# MC-10_Schematics.net
KiCad netlist of a schematic drawn in EAGLE
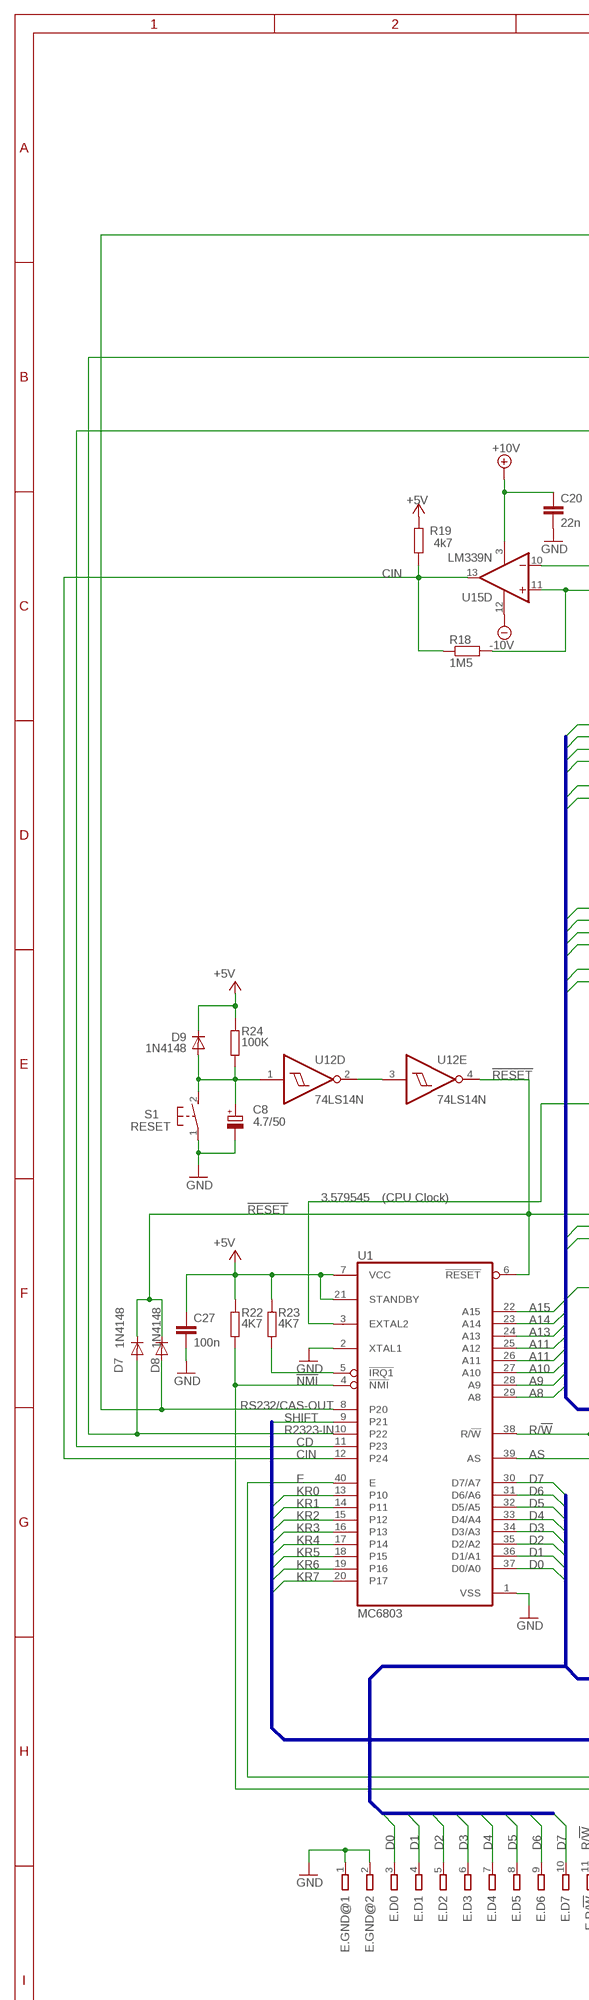
[diagram p0: schematic, sheet 1, part 1 of 2]
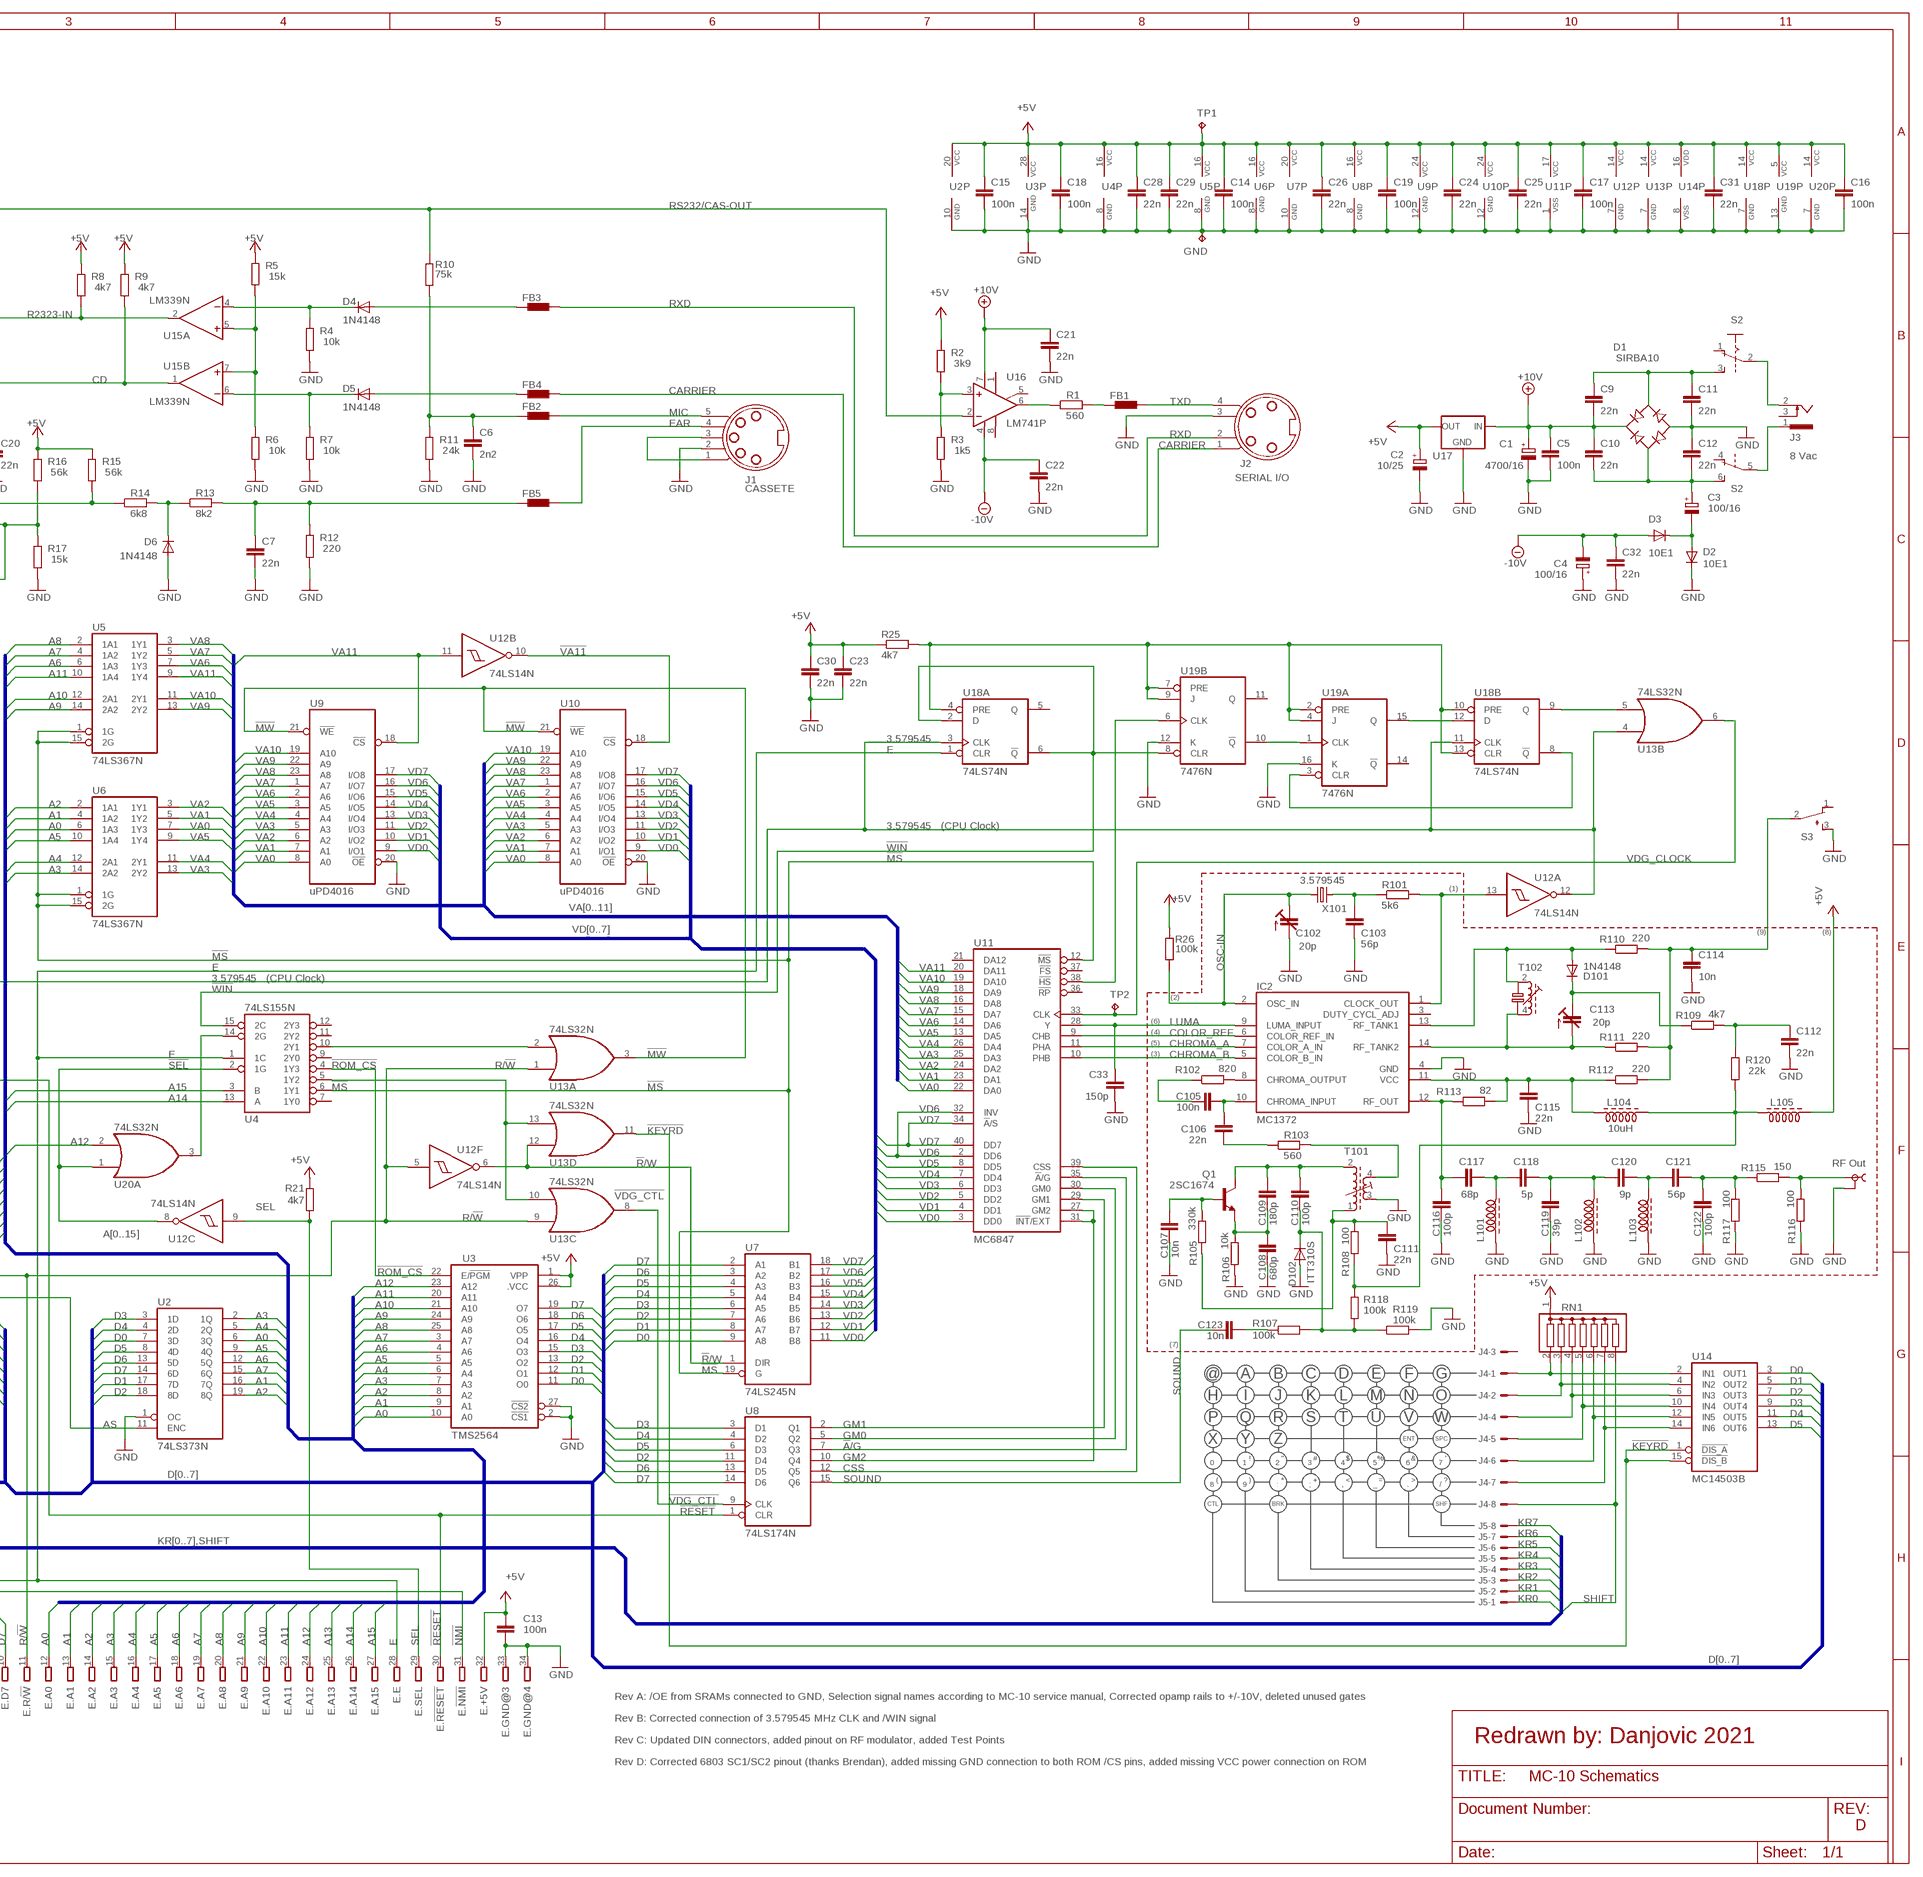
[diagram p1: schematic, sheet 1, part 2 of 2]

(export (version "E")
  (design (tool "Eeschema 10.0.6"))
  (components
    (comp (ref "C1")
      (value "4700/16")
      (footprint "eagle-import:E7,5-18")
      (libsource (lib "eagle-import") (part "CPOL-EUE7.5-18"))
    )
    (comp (ref "C2")
      (value "10/25")
      (footprint "eagle-import:E1,8-4")
      (libsource (lib "eagle-import") (part "CPOL-EUE1.8-4"))
    )
    (comp (ref "C3")
      (value "100/16")
      (footprint "eagle-import:E15-5")
      (libsource (lib "eagle-import") (part "CPOL-EUE15-5AXIAL"))
    )
    (comp (ref "C4")
      (value "100/16")
      (footprint "eagle-import:E15-5")
      (libsource (lib "eagle-import") (part "CPOL-EUE15-5AXIAL"))
    )
    (comp (ref "C5")
      (value "100n")
      (footprint "eagle-import:C050-024X044")
      (libsource (lib "eagle-import") (part "C-EU050-024X044"))
    )
    (comp (ref "C6")
      (value "2n2")
      (footprint "eagle-import:C050-024X044")
      (libsource (lib "eagle-import") (part "C-EU050-024X044"))
    )
    (comp (ref "C7")
      (value "22n")
      (footprint "eagle-import:C050-024X044")
      (libsource (lib "eagle-import") (part "C-EU050-024X044"))
    )
    (comp (ref "C8")
      (value "4.7/50")
      (footprint "eagle-import:E1,8-4")
      (libsource (lib "eagle-import") (part "CPOL-EUE1.8-4"))
    )
    (comp (ref "C9")
      (value "22n")
      (footprint "eagle-import:C050-024X044")
      (libsource (lib "eagle-import") (part "C-EU050-024X044"))
    )
    (comp (ref "C10")
      (value "22n")
      (footprint "eagle-import:C050-024X044")
      (libsource (lib "eagle-import") (part "C-EU050-024X044"))
    )
    (comp (ref "C11")
      (value "22n")
      (footprint "eagle-import:C050-024X044")
      (libsource (lib "eagle-import") (part "C-EU050-024X044"))
    )
    (comp (ref "C12")
      (value "22n")
      (footprint "eagle-import:C050-024X044")
      (libsource (lib "eagle-import") (part "C-EU050-024X044"))
    )
    (comp (ref "C13")
      (value "100n")
      (footprint "eagle-import:C050-024X044")
      (libsource (lib "eagle-import") (part "C-EU050-024X044"))
    )
    (comp (ref "C14")
      (value "100n")
      (footprint "eagle-import:C050-024X044")
      (libsource (lib "eagle-import") (part "C-EU050-024X044"))
    )
    (comp (ref "C15")
      (value "100n")
      (footprint "eagle-import:C050-024X044")
      (libsource (lib "eagle-import") (part "C-EU050-024X044"))
    )
    (comp (ref "C16")
      (value "100n")
      (footprint "eagle-import:C050-024X044")
      (libsource (lib "eagle-import") (part "C-EU050-024X044"))
    )
    (comp (ref "C17")
      (value "100n")
      (footprint "eagle-import:C050-024X044")
      (libsource (lib "eagle-import") (part "C-EU050-024X044"))
    )
    (comp (ref "C18")
      (value "100n")
      (footprint "eagle-import:C050-024X044")
      (libsource (lib "eagle-import") (part "C-EU050-024X044"))
    )
    (comp (ref "C19")
      (value "100n")
      (footprint "eagle-import:C050-024X044")
      (libsource (lib "eagle-import") (part "C-EU050-024X044"))
    )
    (comp (ref "C20")
      (value "22n")
      (footprint "eagle-import:C050-024X044")
      (libsource (lib "eagle-import") (part "C-EU050-024X044"))
    )
    (comp (ref "C21")
      (value "22n")
      (footprint "eagle-import:C050-024X044")
      (libsource (lib "eagle-import") (part "C-EU050-024X044"))
    )
    (comp (ref "C22")
      (value "22n")
      (footprint "eagle-import:C050-024X044")
      (libsource (lib "eagle-import") (part "C-EU050-024X044"))
    )
    (comp (ref "C23")
      (value "22n")
      (footprint "eagle-import:C050-024X044")
      (libsource (lib "eagle-import") (part "C-EU050-024X044"))
    )
    (comp (ref "C24")
      (value "22n")
      (footprint "eagle-import:C050-024X044")
      (libsource (lib "eagle-import") (part "C-EU050-024X044"))
    )
    (comp (ref "C25")
      (value "22n")
      (footprint "eagle-import:C050-024X044")
      (libsource (lib "eagle-import") (part "C-EU050-024X044"))
    )
    (comp (ref "C26")
      (value "22n")
      (footprint "eagle-import:C050-024X044")
      (libsource (lib "eagle-import") (part "C-EU050-024X044"))
    )
    (comp (ref "C27")
      (value "100n")
      (footprint "eagle-import:C050-024X044")
      (libsource (lib "eagle-import") (part "C-EU050-024X044"))
    )
    (comp (ref "C28")
      (value "22n")
      (footprint "eagle-import:C050-024X044")
      (libsource (lib "eagle-import") (part "C-EU050-024X044"))
    )
    (comp (ref "C29")
      (value "22n")
      (footprint "eagle-import:C050-024X044")
      (libsource (lib "eagle-import") (part "C-EU050-024X044"))
    )
    (comp (ref "C30")
      (value "22n")
      (footprint "eagle-import:C050-024X044")
      (libsource (lib "eagle-import") (part "C-EU050-024X044"))
    )
    (comp (ref "C31")
      (value "22n")
      (footprint "eagle-import:C050-024X044")
      (libsource (lib "eagle-import") (part "C-EU050-024X044"))
    )
    (comp (ref "C32")
      (value "22n")
      (footprint "eagle-import:C050-024X044")
      (libsource (lib "eagle-import") (part "C-EU050-024X044"))
    )
    (comp (ref "C33")
      (value "150p")
      (footprint "eagle-import:C025-024X044")
      (libsource (lib "eagle-import") (part "C-EU025-024X044"))
    )
    (comp (ref "C102")
      (value "20p")
      (footprint "eagle-import:3008")
      (libsource (lib "eagle-import") (part "C-TRIMM3008"))
    )
    (comp (ref "C103")
      (value "56p")
      (footprint "eagle-import:C025-024X044")
      (libsource (lib "eagle-import") (part "C-EU025-024X044"))
    )
    (comp (ref "C105")
      (value "100n")
      (footprint "eagle-import:C050-024X044")
      (libsource (lib "eagle-import") (part "C-EU050-024X044"))
    )
    (comp (ref "C106")
      (value "22n")
      (footprint "eagle-import:C050-024X044")
      (libsource (lib "eagle-import") (part "C-EU050-024X044"))
    )
    (comp (ref "C107")
      (value "10n")
      (footprint "eagle-import:C025-024X044")
      (libsource (lib "eagle-import") (part "C-EU025-024X044"))
    )
    (comp (ref "C108")
      (value "680p")
      (footprint "eagle-import:C025-024X044")
      (libsource (lib "eagle-import") (part "C-EU025-024X044"))
    )
    (comp (ref "C109")
      (value "180p")
      (footprint "eagle-import:C025-024X044")
      (libsource (lib "eagle-import") (part "C-EU025-024X044"))
    )
    (comp (ref "C110")
      (value "100p")
      (footprint "eagle-import:C025-024X044")
      (libsource (lib "eagle-import") (part "C-EU025-024X044"))
    )
    (comp (ref "C111")
      (value "22n")
      (footprint "eagle-import:C025-024X044")
      (libsource (lib "eagle-import") (part "C-EU025-024X044"))
    )
    (comp (ref "C112")
      (value "22n")
      (footprint "eagle-import:C025-024X044")
      (libsource (lib "eagle-import") (part "C-EU025-024X044"))
    )
    (comp (ref "C113")
      (value "20p")
      (footprint "eagle-import:3008")
      (libsource (lib "eagle-import") (part "C-TRIMM3008"))
    )
    (comp (ref "C114")
      (value "10n")
      (footprint "eagle-import:C025-024X044")
      (libsource (lib "eagle-import") (part "C-EU025-024X044"))
    )
    (comp (ref "C115")
      (value "22n")
      (footprint "eagle-import:C025-024X044")
      (libsource (lib "eagle-import") (part "C-EU025-024X044"))
    )
    (comp (ref "C116")
      (value "100p")
      (footprint "eagle-import:C025-024X044")
      (libsource (lib "eagle-import") (part "C-EU025-024X044"))
    )
    (comp (ref "C117")
      (value "68p")
      (footprint "eagle-import:C025-024X044")
      (libsource (lib "eagle-import") (part "C-EU025-024X044"))
    )
    (comp (ref "C118")
      (value "5p")
      (footprint "eagle-import:C025-024X044")
      (libsource (lib "eagle-import") (part "C-EU025-024X044"))
    )
    (comp (ref "C119")
      (value "39p")
      (footprint "eagle-import:C025-024X044")
      (libsource (lib "eagle-import") (part "C-EU025-024X044"))
    )
    (comp (ref "C120")
      (value "9p")
      (footprint "eagle-import:C025-024X044")
      (libsource (lib "eagle-import") (part "C-EU025-024X044"))
    )
    (comp (ref "C121")
      (value "56p")
      (footprint "eagle-import:C025-024X044")
      (libsource (lib "eagle-import") (part "C-EU025-024X044"))
    )
    (comp (ref "C122")
      (value "100p")
      (footprint "eagle-import:C025-024X044")
      (libsource (lib "eagle-import") (part "C-EU025-024X044"))
    )
    (comp (ref "C123")
      (value "10n")
      (footprint "eagle-import:C025-024X044")
      (libsource (lib "eagle-import") (part "C-EU025-024X044"))
    )
    (comp (ref "D1")
      (value "SIRBA10")
      (footprint "eagle-import:SKBB")
      (libsource (lib "eagle-import") (part "RECTIFIER-SKBB"))
    )
    (comp (ref "D2")
      (value "10E1")
      (footprint "eagle-import:D-7.5")
      (libsource (lib "eagle-import") (part "DIODE-D-7.5"))
    )
    (comp (ref "D3")
      (value "10E1")
      (footprint "eagle-import:D-7.5")
      (libsource (lib "eagle-import") (part "DIODE-D-7.5"))
    )
    (comp (ref "D4")
      (value "1N4148")
      (footprint "eagle-import:DO35-7")
      (libsource (lib "eagle-import") (part "1N4148DO35-7"))
    )
    (comp (ref "D5")
      (value "1N4148")
      (footprint "eagle-import:DO35-7")
      (libsource (lib "eagle-import") (part "1N4148DO35-7"))
    )
    (comp (ref "D6")
      (value "1N4148")
      (footprint "eagle-import:DO35-7")
      (libsource (lib "eagle-import") (part "1N4148DO35-7"))
    )
    (comp (ref "D7")
      (value "1N4148")
      (footprint "eagle-import:DO35-7")
      (libsource (lib "eagle-import") (part "1N4148DO35-7"))
    )
    (comp (ref "D8")
      (value "1N4148")
      (footprint "eagle-import:DO35-7")
      (libsource (lib "eagle-import") (part "1N4148DO35-7"))
    )
    (comp (ref "D9")
      (value "1N4148")
      (footprint "eagle-import:DO35-7")
      (libsource (lib "eagle-import") (part "1N4148DO35-7"))
    )
    (comp (ref "D101")
      (value "1N4148")
      (footprint "eagle-import:DO35-7")
      (libsource (lib "eagle-import") (part "1N4148DO35-7"))
    )
    (comp (ref "D102")
      (value "ITT310S")
      (footprint "eagle-import:DO35-7")
      (libsource (lib "eagle-import") (part "1N4148DO35-7"))
    )
    (comp (ref "E.")
      (value "EXPANSION")
      (footprint "eagle-import:EXPANSION_PORT")
      (libsource (lib "eagle-import") (part "EXPANSION"))
    )
    (comp (ref "FB1")
      (value "BL01RN1A")
      (footprint "eagle-import:BL01RN1A")
      (libsource (lib "eagle-import") (part "BL01RN1A"))
    )
    (comp (ref "FB2")
      (value "BL01RN1A")
      (footprint "eagle-import:BL01RN1A")
      (libsource (lib "eagle-import") (part "BL01RN1A"))
    )
    (comp (ref "FB3")
      (value "BL01RN1A")
      (footprint "eagle-import:BL01RN1A")
      (libsource (lib "eagle-import") (part "BL01RN1A"))
    )
    (comp (ref "FB4")
      (value "BL01RN1A")
      (footprint "eagle-import:BL01RN1A")
      (libsource (lib "eagle-import") (part "BL01RN1A"))
    )
    (comp (ref "FB5")
      (value "BL01RN1A")
      (footprint "eagle-import:BL01RN1A")
      (libsource (lib "eagle-import") (part "BL01RN1A"))
    )
    (comp (ref "GND")
      (value "TPPAD1-13")
      (footprint "eagle-import:P1-13")
      (libsource (lib "eagle-import") (part "TPPAD1-13"))
    )
    (comp (ref "IC2")
      (value "MC1372")
      (footprint "eagle-import:DIL14")
      (libsource (lib "eagle-import") (part "MC1372"))
    )
    (comp (ref "J1")
      (value "DS-4-05")
      (footprint "eagle-import:MC-10_DIN05S")
      (libsource (lib "eagle-import") (part "DS-4-05"))
    )
    (comp (ref "J2")
      (value "DS-4-04")
      (footprint "eagle-import:MC-10_DIN04S")
      (libsource (lib "eagle-import") (part "DS-4-04"))
    )
    (comp (ref "J3")
      (value "733980-62")
      (footprint "eagle-import:733980-62")
      (libsource (lib "eagle-import") (part "73398?0-62"))
    )
    (comp (ref "J4")
      (value "22-27-2081-08")
      (footprint "eagle-import:6410-08")
      (libsource (lib "eagle-import") (part "22-?-0827-2081"))
    )
    (comp (ref "J5")
      (value "22-27-2081-08")
      (footprint "eagle-import:6410-08")
      (libsource (lib "eagle-import") (part "22-?-0827-2081"))
    )
    (comp (ref "L101")
      (value "Z15/05CCW")
      (footprint "eagle-import:Z15_05")
      (libsource (lib "eagle-import") (part "Z?CCW15/05"))
    )
    (comp (ref "L102")
      (value "Z15/05CCW")
      (footprint "eagle-import:Z15_05")
      (libsource (lib "eagle-import") (part "Z?CCW15/05"))
    )
    (comp (ref "L103")
      (value "Z15/05CCW")
      (footprint "eagle-import:Z15_05")
      (libsource (lib "eagle-import") (part "Z?CCW15/05"))
    )
    (comp (ref "L104")
      (value "10uH")
      (footprint "eagle-import:Z15_05")
      (libsource (lib "eagle-import") (part "Z?CCW15/05"))
    )
    (comp (ref "L105")
      (value "10uH")
      (footprint "eagle-import:Z15_05")
      (libsource (lib "eagle-import") (part "Z?CCW15/05"))
    )
    (comp (ref "Q1")
      (value "2SC1674")
      (footprint "eagle-import:TO92-CEB")
      (libsource (lib "eagle-import") (part "-NPN-TO92-CEBBF494"))
    )
    (comp (ref "R1")
      (value "560")
      (footprint "eagle-import:0204_7")
      (libsource (lib "eagle-import") (part "R-EU_0204/7"))
    )
    (comp (ref "R2")
      (value "3k9")
      (footprint "eagle-import:0204_7")
      (libsource (lib "eagle-import") (part "R-EU_0204/7"))
    )
    (comp (ref "R3")
      (value "1k5")
      (footprint "eagle-import:0204_7")
      (libsource (lib "eagle-import") (part "R-EU_0204/7"))
    )
    (comp (ref "R4")
      (value "10k")
      (footprint "eagle-import:0204_7")
      (libsource (lib "eagle-import") (part "R-EU_0204/7"))
    )
    (comp (ref "R5")
      (value "15k")
      (footprint "eagle-import:0204_7")
      (libsource (lib "eagle-import") (part "R-EU_0204/7"))
    )
    (comp (ref "R6")
      (value "10k")
      (footprint "eagle-import:0204_7")
      (libsource (lib "eagle-import") (part "R-EU_0204/7"))
    )
    (comp (ref "R7")
      (value "10k")
      (footprint "eagle-import:0204_7")
      (libsource (lib "eagle-import") (part "R-EU_0204/7"))
    )
    (comp (ref "R8")
      (value "4k7")
      (footprint "eagle-import:0204_7")
      (libsource (lib "eagle-import") (part "R-EU_0204/7"))
    )
    (comp (ref "R9")
      (value "4k7")
      (footprint "eagle-import:0204_7")
      (libsource (lib "eagle-import") (part "R-EU_0204/7"))
    )
    (comp (ref "R10")
      (value "75k")
      (footprint "eagle-import:0204_7")
      (libsource (lib "eagle-import") (part "R-EU_0204/7"))
    )
    (comp (ref "R11")
      (value "24k")
      (footprint "eagle-import:0204_7")
      (libsource (lib "eagle-import") (part "R-EU_0204/7"))
    )
    (comp (ref "R12")
      (value "220")
      (footprint "eagle-import:0204_7")
      (libsource (lib "eagle-import") (part "R-EU_0204/7"))
    )
    (comp (ref "R13")
      (value "8k2")
      (footprint "eagle-import:0204_7")
      (libsource (lib "eagle-import") (part "R-EU_0204/7"))
    )
    (comp (ref "R14")
      (value "6k8")
      (footprint "eagle-import:0204_7")
      (libsource (lib "eagle-import") (part "R-EU_0204/7"))
    )
    (comp (ref "R15")
      (value "56k")
      (footprint "eagle-import:0204_7")
      (libsource (lib "eagle-import") (part "R-EU_0204/7"))
    )
    (comp (ref "R16")
      (value "56k")
      (footprint "eagle-import:0204_7")
      (libsource (lib "eagle-import") (part "R-EU_0204/7"))
    )
    (comp (ref "R17")
      (value "15k")
      (footprint "eagle-import:0204_7")
      (libsource (lib "eagle-import") (part "R-EU_0204/7"))
    )
    (comp (ref "R18")
      (value "1M5")
      (footprint "eagle-import:0204_7")
      (libsource (lib "eagle-import") (part "R-EU_0204/7"))
    )
    (comp (ref "R19")
      (value "4k7")
      (footprint "eagle-import:0204_7")
      (libsource (lib "eagle-import") (part "R-EU_0204/7"))
    )
    (comp (ref "R21")
      (value "4k7")
      (footprint "eagle-import:0204_7")
      (libsource (lib "eagle-import") (part "R-EU_0204/7"))
    )
    (comp (ref "R22")
      (value "4K7")
      (footprint "eagle-import:0204_7")
      (libsource (lib "eagle-import") (part "R-EU_0204/7"))
    )
    (comp (ref "R23")
      (value "4K7")
      (footprint "eagle-import:0204_7")
      (libsource (lib "eagle-import") (part "R-EU_0204/7"))
    )
    (comp (ref "R24")
      (value "100K")
      (footprint "eagle-import:0204_7")
      (libsource (lib "eagle-import") (part "R-EU_0204/7"))
    )
    (comp (ref "R25")
      (value "4k7")
      (footprint "eagle-import:0204_7")
      (libsource (lib "eagle-import") (part "R-EU_0204/7"))
    )
    (comp (ref "R26")
      (value "100k")
      (footprint "eagle-import:0204_7")
      (libsource (lib "eagle-import") (part "R-EU_0204/7"))
    )
    (comp (ref "R101")
      (value "5k6")
      (footprint "eagle-import:0204_7")
      (libsource (lib "eagle-import") (part "R-EU_0204/7"))
    )
    (comp (ref "R102")
      (value "820")
      (footprint "eagle-import:0204_7")
      (libsource (lib "eagle-import") (part "R-EU_0204/7"))
    )
    (comp (ref "R103")
      (value "560")
      (footprint "eagle-import:0204_7")
      (libsource (lib "eagle-import") (part "R-EU_0204/7"))
    )
    (comp (ref "R105")
      (value "330k")
      (footprint "eagle-import:0204_7")
      (libsource (lib "eagle-import") (part "R-EU_0204/7"))
    )
    (comp (ref "R106")
      (value "10k")
      (footprint "eagle-import:0204_7")
      (libsource (lib "eagle-import") (part "R-EU_0204/7"))
    )
    (comp (ref "R107")
      (value "100k")
      (footprint "eagle-import:0204_7")
      (libsource (lib "eagle-import") (part "R-EU_0204/7"))
    )
    (comp (ref "R108")
      (value "100")
      (footprint "eagle-import:0204_7")
      (libsource (lib "eagle-import") (part "R-EU_0204/7"))
    )
    (comp (ref "R109")
      (value "4k7")
      (footprint "eagle-import:0204_7")
      (libsource (lib "eagle-import") (part "R-EU_0204/7"))
    )
    (comp (ref "R110")
      (value "220")
      (footprint "eagle-import:0204_7")
      (libsource (lib "eagle-import") (part "R-EU_0204/7"))
    )
    (comp (ref "R111")
      (value "220")
      (footprint "eagle-import:0204_7")
      (libsource (lib "eagle-import") (part "R-EU_0204/7"))
    )
    (comp (ref "R112")
      (value "220")
      (footprint "eagle-import:0204_7")
      (libsource (lib "eagle-import") (part "R-EU_0204/7"))
    )
    (comp (ref "R113")
      (value "82")
      (footprint "eagle-import:0204_7")
      (libsource (lib "eagle-import") (part "R-EU_0204/7"))
    )
    (comp (ref "R115")
      (value "150")
      (footprint "eagle-import:0204_7")
      (libsource (lib "eagle-import") (part "R-EU_0204/7"))
    )
    (comp (ref "R116")
      (value "100")
      (footprint "eagle-import:0204_7")
      (libsource (lib "eagle-import") (part "R-EU_0204/7"))
    )
    (comp (ref "R117")
      (value "100")
      (footprint "eagle-import:0204_7")
      (libsource (lib "eagle-import") (part "R-EU_0204/7"))
    )
    (comp (ref "R118")
      (value "100k")
      (footprint "eagle-import:0204_7")
      (libsource (lib "eagle-import") (part "R-EU_0204/7"))
    )
    (comp (ref "R119")
      (value "100k")
      (footprint "eagle-import:0204_7")
      (libsource (lib "eagle-import") (part "R-EU_0204/7"))
    )
    (comp (ref "R120")
      (value "22k")
      (footprint "eagle-import:0204_7")
      (libsource (lib "eagle-import") (part "R-EU_0204/7"))
    )
    (comp (ref "RN1")
      (value "G07R")
      (footprint "eagle-import:SIL8")
      (libsource (lib "eagle-import") (part "G07R"))
    )
    (comp (ref "S1")
      (value "RESET")
      (footprint "eagle-import:B3F-31XX")
      (fields (field (name "MPN") "B3F-3100"))
      (libsource (lib "eagle-import") (part "31-XX"))
    )
    (comp (ref "S2")
      (value "A68-A31")
      (footprint "eagle-import:A68-A31")
      (libsource (lib "eagle-import") (part "A68-A31"))
    )
    (comp (ref "S3")
      (value "TL32PO")
      (footprint "eagle-import:TL3XPO")
      (libsource (lib "eagle-import") (part "TL32PO"))
    )
    (comp (ref "T101")
      (value "71-4-2143")
      (footprint "eagle-import:71-5")
      (libsource (lib "eagle-import") (part "71-4-2143"))
    )
    (comp (ref "T102")
      (value "71K1-2-4")
      (footprint "eagle-import:71K")
      (libsource (lib "eagle-import") (part "71K1-2-4"))
    )
    (comp (ref "TP1")
      (value "TPPAD1-13")
      (footprint "eagle-import:P1-13")
      (libsource (lib "eagle-import") (part "TPPAD1-13"))
    )
    (comp (ref "TP2")
      (value "TPPAD1-13")
      (footprint "eagle-import:P1-13")
      (libsource (lib "eagle-import") (part "TPPAD1-13"))
    )
    (comp (ref "U1")
      (value "MC6803")
      (footprint "eagle-import:DIL40")
      (libsource (lib "eagle-import") (part "MC6803P"))
    )
    (comp (ref "U2")
      (value "74LS373N")
      (footprint "eagle-import:DIL20")
      (libsource (lib "eagle-import") (part "74373NLS"))
    )
    (comp (ref "U3")
      (value "TMS2564")
      (footprint "eagle-import:DIL28")
      (libsource (lib "eagle-import") (part "TMS2564JL"))
    )
    (comp (ref "U4")
      (value "74LS155N")
      (footprint "eagle-import:DIL16")
      (libsource (lib "eagle-import") (part "74155NLS"))
    )
    (comp (ref "U5")
      (value "74LS367N")
      (footprint "eagle-import:DIL16")
      (libsource (lib "eagle-import") (part "74367NHC"))
    )
    (comp (ref "U6")
      (value "74LS367N")
      (footprint "eagle-import:DIL16")
      (libsource (lib "eagle-import") (part "74367NHC"))
    )
    (comp (ref "U7")
      (value "74LS245N")
      (footprint "eagle-import:DIL20")
      (libsource (lib "eagle-import") (part "74245NLS"))
    )
    (comp (ref "U8")
      (value "74LS174N")
      (footprint "eagle-import:DIL16")
      (libsource (lib "eagle-import") (part "74174NLS"))
    )
    (comp (ref "U9")
      (value "uPD4016")
      (footprint "eagle-import:DIL24")
      (libsource (lib "eagle-import") (part "UPD4016{dblquote}"))
    )
    (comp (ref "U10")
      (value "uPD4016")
      (footprint "eagle-import:DIL24")
      (libsource (lib "eagle-import") (part "UPD4016{dblquote}"))
    )
    (comp (ref "U11")
      (value "MC6847")
      (footprint "eagle-import:DIL40")
      (libsource (lib "eagle-import") (part "MC6847"))
    )
    (comp (ref "U12")
      (value "74LS14N")
      (footprint "eagle-import:DIL14")
      (libsource (lib "eagle-import") (part "7414NLS"))
    )
    (comp (ref "U13")
      (value "74LS32N")
      (footprint "eagle-import:DIL14")
      (libsource (lib "eagle-import") (part "7432NLS"))
    )
    (comp (ref "U14")
      (value "MC14503B")
      (footprint "eagle-import:DIL16")
      (libsource (lib "eagle-import") (part "MC14503BN"))
    )
    (comp (ref "U15")
      (value "LM339N")
      (footprint "eagle-import:DIL14")
      (libsource (lib "eagle-import") (part "LM339N"))
    )
    (comp (ref "U16")
      (value "LM741P")
      (footprint "eagle-import:DIL08")
      (libsource (lib "eagle-import") (part "741PLM"))
    )
    (comp (ref "U17")
      (value "78XXL")
      (footprint "eagle-import:78XXL")
      (libsource (lib "eagle-import") (part "78XXL"))
    )
    (comp (ref "U18")
      (value "74LS74N")
      (footprint "eagle-import:DIL14")
      (libsource (lib "eagle-import") (part "7474NLS"))
    )
    (comp (ref "U19")
      (value "7476N")
      (footprint "eagle-import:DIL16")
      (libsource (lib "eagle-import") (part "7476N"))
    )
    (comp (ref "U20")
      (value "74LS32N")
      (footprint "eagle-import:DIL14")
      (libsource (lib "eagle-import") (part "7432NLS"))
    )
    (comp (ref "X1")
      (value "RF Out")
      (footprint "eagle-import:TOBU3")
      (fields (field (name "MF") "FARNELL") (field (name "MPN") "TOBU 3"))
      (libsource (lib "eagle-import") (part "TOBU3"))
    )
    (comp (ref "X101")
      (value "3.579545")
      (footprint "eagle-import:HC49U70")
      (libsource (lib "eagle-import") (part "CRYSTALHC49U70"))
    )
  )
  (nets
    (net (code "1") (name "+5V") (class "Default")
      (node (ref "C13") (pin "1") (pinfunction "1_1") (pintype "passive"))
      (node (ref "C14") (pin "1") (pinfunction "1_1") (pintype "passive"))
      (node (ref "C15") (pin "1") (pinfunction "1_1") (pintype "passive"))
      (node (ref "C16") (pin "1") (pinfunction "1_1") (pintype "passive"))
      (node (ref "C17") (pin "1") (pinfunction "1_1") (pintype "passive"))
      (node (ref "C18") (pin "1") (pinfunction "1_1") (pintype "passive"))
      (node (ref "C19") (pin "1") (pinfunction "1_1") (pintype "passive"))
      (node (ref "C2") (pin "+") (pinfunction "+_+") (pintype "passive"))
      (node (ref "C23") (pin "1") (pinfunction "1_1") (pintype "passive"))
      (node (ref "C24") (pin "1") (pinfunction "1_1") (pintype "passive"))
      (node (ref "C25") (pin "1") (pinfunction "1_1") (pintype "passive"))
      (node (ref "C26") (pin "1") (pinfunction "1_1") (pintype "passive"))
      (node (ref "C27") (pin "1") (pinfunction "1_1") (pintype "passive"))
      (node (ref "C28") (pin "1") (pinfunction "1_1") (pintype "passive"))
      (node (ref "C29") (pin "1") (pinfunction "1_1") (pintype "passive"))
      (node (ref "C30") (pin "1") (pinfunction "1_1") (pintype "passive"))
      (node (ref "C31") (pin "1") (pinfunction "1_1") (pintype "passive"))
      (node (ref "D9") (pin "C") (pinfunction "C_C") (pintype "passive"))
      (node (ref "E.") (pin "32") (pinfunction "P_32") (pintype "bidirectional"))
      (node (ref "L105") (pin "1") (pinfunction "1_1") (pintype "passive"))
      (node (ref "R15") (pin "2") (pinfunction "2_2") (pintype "passive"))
      (node (ref "R16") (pin "2") (pinfunction "2_2") (pintype "passive"))
      (node (ref "R19") (pin "2") (pinfunction "2_2") (pintype "passive"))
      (node (ref "R2") (pin "2") (pinfunction "2_2") (pintype "passive"))
      (node (ref "R21") (pin "1") (pinfunction "1_1") (pintype "passive"))
      (node (ref "R22") (pin "1") (pinfunction "1_1") (pintype "passive"))
      (node (ref "R23") (pin "1") (pinfunction "1_1") (pintype "passive"))
      (node (ref "R24") (pin "1") (pinfunction "1_1") (pintype "passive"))
      (node (ref "R25") (pin "1") (pinfunction "1_1") (pintype "passive"))
      (node (ref "R26") (pin "2") (pinfunction "2_2") (pintype "passive"))
      (node (ref "R5") (pin "2") (pinfunction "2_2") (pintype "passive"))
      (node (ref "R8") (pin "2") (pinfunction "2_2") (pintype "passive"))
      (node (ref "R9") (pin "2") (pinfunction "2_2") (pintype "passive"))
      (node (ref "RN1") (pin "1") (pinfunction "1_1") (pintype "passive"))
      (node (ref "TP1") (pin "TP") (pinfunction "TP_TP") (pintype "input"))
      (node (ref "U1") (pin "21") (pinfunction "STANDBY_21") (pintype "input"))
      (node (ref "U1") (pin "7") (pinfunction "VCC_7") (pintype "power_in"))
      (node (ref "U10") (pin "24") (pinfunction "VCC_24") (pintype "power_in"))
      (node (ref "U11") (pin "17") (pinfunction "VCC_17") (pintype "power_in"))
      (node (ref "U12") (pin "14") (pinfunction "VCC_14") (pintype "power_in"))
      (node (ref "U13") (pin "14") (pinfunction "VCC_14") (pintype "power_in"))
      (node (ref "U14") (pin "16") (pinfunction "VDD_16") (pintype "power_in"))
      (node (ref "U17") (pin "OUT") (pinfunction "OUT_OUT") (pintype "passive"))
      (node (ref "U18") (pin "14") (pinfunction "VCC_14") (pintype "power_in"))
      (node (ref "U19") (pin "5") (pinfunction "VCC_5") (pintype "power_in"))
      (node (ref "U2") (pin "20") (pinfunction "VCC_20") (pintype "power_in"))
      (node (ref "U20") (pin "14") (pinfunction "VCC_14") (pintype "power_in"))
      (node (ref "U3") (pin "1") (pinfunction "VPP_1") (pintype "input"))
      (node (ref "U3") (pin "26") (pinfunction ".VCC_26") (pintype "input"))
      (node (ref "U3") (pin "28") (pinfunction "VCC_28") (pintype "power_in"))
      (node (ref "U4") (pin "16") (pinfunction "VCC_16") (pintype "power_in"))
      (node (ref "U5") (pin "16") (pinfunction "VCC_16") (pintype "power_in"))
      (node (ref "U6") (pin "16") (pinfunction "VCC_16") (pintype "power_in"))
      (node (ref "U7") (pin "20") (pinfunction "VCC_20") (pintype "power_in"))
      (node (ref "U8") (pin "16") (pinfunction "VCC_16") (pintype "power_in"))
      (node (ref "U9") (pin "24") (pinfunction "VCC_24") (pintype "power_in"))
    )
    (net (code "2") (name "+10V") (class "Default")
      (node (ref "C1") (pin "+") (pinfunction "+_+") (pintype "passive"))
      (node (ref "C10") (pin "1") (pinfunction "1_1") (pintype "passive"))
      (node (ref "C20") (pin "1") (pinfunction "1_1") (pintype "passive"))
      (node (ref "C21") (pin "1") (pinfunction "1_1") (pintype "passive"))
      (node (ref "C5") (pin "1") (pinfunction "1_1") (pintype "passive"))
      (node (ref "C9") (pin "2") (pinfunction "2_2") (pintype "passive"))
      (node (ref "D1") (pin "+") (pinfunction "+_+") (pintype "passive"))
      (node (ref "U15") (pin "3") (pinfunction "V+_3") (pintype "power_in"))
      (node (ref "U16") (pin "7") (pinfunction "V+_7") (pintype "power_in"))
      (node (ref "U17") (pin "IN") (pinfunction "IN_IN") (pintype "input"))
    )
    (net (code "3") (name "-10V") (class "Default")
      (node (ref "C22") (pin "1") (pinfunction "1_1") (pintype "passive"))
      (node (ref "C32") (pin "1") (pinfunction "1_1") (pintype "passive"))
      (node (ref "C4") (pin "-") (pinfunction "-_-") (pintype "passive"))
      (node (ref "D3") (pin "A") (pinfunction "A_A") (pintype "passive"))
      (node (ref "U15") (pin "12") (pinfunction "GND_12") (pintype "power_in"))
      (node (ref "U16") (pin "4") (pinfunction "V-_4") (pintype "power_in"))
    )
    (net (code "9") (name "3.579545") (class "Default")
      (node (ref "U1") (pin "3") (pinfunction "EXTAL2_3") (pintype "input"))
      (node (ref "U12") (pin "12") (pinfunction "O_12") (pintype "output"))
      (node (ref "U13") (pin "4") (pinfunction "I0_4") (pintype "input"))
      (node (ref "U18") (pin "11") (pinfunction "CLK_11") (pintype "input"))
      (node (ref "U18") (pin "3") (pinfunction "CLK_3") (pintype "input"))
    )
    (net (code "10") (name "A0") (class "Default")
      (node (ref "E.") (pin "12") (pinfunction "P_12") (pintype "bidirectional"))
      (node (ref "U2") (pin "6") (pinfunction "3Q_6") (pintype "tri_state"))
      (node (ref "U3") (pin "10") (pinfunction "A0_10") (pintype "input"))
      (node (ref "U6") (pin "6") (pinfunction "1A3_6") (pintype "input"))
    )
    (net (code "11") (name "A1") (class "Default")
      (node (ref "E.") (pin "13") (pinfunction "P_13") (pintype "bidirectional"))
      (node (ref "U2") (pin "16") (pinfunction "7Q_16") (pintype "tri_state"))
      (node (ref "U3") (pin "9") (pinfunction "A1_9") (pintype "input"))
      (node (ref "U6") (pin "4") (pinfunction "1A2_4") (pintype "input"))
    )
    (net (code "12") (name "A2") (class "Default")
      (node (ref "E.") (pin "14") (pinfunction "P_14") (pintype "bidirectional"))
      (node (ref "U2") (pin "19") (pinfunction "8Q_19") (pintype "tri_state"))
      (node (ref "U3") (pin "8") (pinfunction "A2_8") (pintype "input"))
      (node (ref "U6") (pin "2") (pinfunction "1A1_2") (pintype "input"))
    )
    (net (code "13") (name "A3") (class "Default")
      (node (ref "E.") (pin "15") (pinfunction "P_15") (pintype "bidirectional"))
      (node (ref "U2") (pin "2") (pinfunction "1Q_2") (pintype "tri_state"))
      (node (ref "U3") (pin "7") (pinfunction "A3_7") (pintype "input"))
      (node (ref "U6") (pin "14") (pinfunction "2A2_14") (pintype "input"))
    )
    (net (code "14") (name "A4") (class "Default")
      (node (ref "E.") (pin "16") (pinfunction "P_16") (pintype "bidirectional"))
      (node (ref "U2") (pin "5") (pinfunction "2Q_5") (pintype "tri_state"))
      (node (ref "U3") (pin "6") (pinfunction "A4_6") (pintype "input"))
      (node (ref "U6") (pin "12") (pinfunction "2A1_12") (pintype "input"))
    )
    (net (code "15") (name "A5") (class "Default")
      (node (ref "E.") (pin "17") (pinfunction "P_17") (pintype "bidirectional"))
      (node (ref "U2") (pin "9") (pinfunction "4Q_9") (pintype "tri_state"))
      (node (ref "U3") (pin "5") (pinfunction "A5_5") (pintype "input"))
      (node (ref "U6") (pin "10") (pinfunction "1A4_10") (pintype "input"))
    )
    (net (code "16") (name "A6") (class "Default")
      (node (ref "E.") (pin "18") (pinfunction "P_18") (pintype "bidirectional"))
      (node (ref "U2") (pin "12") (pinfunction "5Q_12") (pintype "tri_state"))
      (node (ref "U3") (pin "4") (pinfunction "A6_4") (pintype "input"))
      (node (ref "U5") (pin "6") (pinfunction "1A3_6") (pintype "input"))
    )
    (net (code "17") (name "A7") (class "Default")
      (node (ref "E.") (pin "19") (pinfunction "P_19") (pintype "bidirectional"))
      (node (ref "U2") (pin "15") (pinfunction "6Q_15") (pintype "tri_state"))
      (node (ref "U3") (pin "3") (pinfunction "A7_3") (pintype "input"))
      (node (ref "U5") (pin "4") (pinfunction "1A2_4") (pintype "input"))
    )
    (net (code "18") (name "A8") (class "Default")
      (node (ref "E.") (pin "20") (pinfunction "P_20") (pintype "bidirectional"))
      (node (ref "U1") (pin "29") (pinfunction "A8_29") (pintype "bidirectional"))
      (node (ref "U3") (pin "25") (pinfunction "A8_25") (pintype "input"))
      (node (ref "U5") (pin "2") (pinfunction "1A1_2") (pintype "input"))
    )
    (net (code "19") (name "A9") (class "Default")
      (node (ref "E.") (pin "21") (pinfunction "P_21") (pintype "bidirectional"))
      (node (ref "U1") (pin "28") (pinfunction "A9_28") (pintype "bidirectional"))
      (node (ref "U3") (pin "24") (pinfunction "A9_24") (pintype "input"))
      (node (ref "U5") (pin "14") (pinfunction "2A2_14") (pintype "input"))
    )
    (net (code "20") (name "A10") (class "Default")
      (node (ref "E.") (pin "22") (pinfunction "P_22") (pintype "bidirectional"))
      (node (ref "U1") (pin "27") (pinfunction "A10_27") (pintype "bidirectional"))
      (node (ref "U3") (pin "21") (pinfunction "A10_21") (pintype "input"))
      (node (ref "U5") (pin "12") (pinfunction "2A1_12") (pintype "input"))
    )
    (net (code "21") (name "A11") (class "Default")
      (node (ref "E.") (pin "23") (pinfunction "P_23") (pintype "bidirectional"))
      (node (ref "U1") (pin "25") (pinfunction "A12_25") (pintype "bidirectional"))
      (node (ref "U1") (pin "26") (pinfunction "A11_26") (pintype "bidirectional"))
      (node (ref "U3") (pin "20") (pinfunction "A11_20") (pintype "input"))
      (node (ref "U5") (pin "10") (pinfunction "1A4_10") (pintype "input"))
    )
    (net (code "22") (name "A12") (class "Default")
      (node (ref "E.") (pin "24") (pinfunction "P_24") (pintype "bidirectional"))
      (node (ref "U20") (pin "2") (pinfunction "I1_2") (pintype "input"))
      (node (ref "U3") (pin "23") (pinfunction "A12_23") (pintype "input"))
    )
    (net (code "23") (name "A13") (class "Default")
      (node (ref "E.") (pin "25") (pinfunction "P_25") (pintype "bidirectional"))
      (node (ref "U1") (pin "24") (pinfunction "A13_24") (pintype "bidirectional"))
    )
    (net (code "24") (name "A14") (class "Default")
      (node (ref "E.") (pin "26") (pinfunction "P_26") (pintype "bidirectional"))
      (node (ref "U1") (pin "23") (pinfunction "A14_23") (pintype "bidirectional"))
      (node (ref "U4") (pin "13") (pinfunction "A_13") (pintype "input"))
    )
    (net (code "25") (name "A15") (class "Default")
      (node (ref "E.") (pin "27") (pinfunction "P_27") (pintype "bidirectional"))
      (node (ref "U1") (pin "22") (pinfunction "A15_22") (pintype "bidirectional"))
      (node (ref "U4") (pin "3") (pinfunction "B_3") (pintype "input"))
    )
    (net (code "26") (name "AS") (class "Default")
      (node (ref "U1") (pin "39") (pinfunction "AS_39") (pintype "output"))
      (node (ref "U2") (pin "11") (pinfunction "ENC_11") (pintype "input"))
    )
    (net (code "27") (name "CARRIER") (class "Default")
      (node (ref "FB4") (pin "2") (pinfunction "2_2") (pintype "passive"))
      (node (ref "J2") (pin "1") (pinfunction "1_1") (pintype "passive"))
    )
    (net (code "28") (name "CD") (class "Default")
      (node (ref "R9") (pin "1") (pinfunction "1_1") (pintype "passive"))
      (node (ref "U1") (pin "11") (pinfunction "P23_11") (pintype "bidirectional"))
      (node (ref "U15") (pin "1") (pinfunction "OUT_1") (pintype "open_collector"))
    )
    (net (code "29") (name "CHROMA_A") (class "Default")
      (node (ref "IC2") (pin "7") (pinfunction "COLOR_A_IN_7") (pintype "input"))
      (node (ref "U11") (pin "11") (pinfunction "PHA_11") (pintype "output"))
    )
    (net (code "30") (name "CHROMA_B") (class "Default")
      (node (ref "IC2") (pin "5") (pinfunction "COLOR_B_IN_5") (pintype "input"))
      (node (ref "U11") (pin "10") (pinfunction "PHB_10") (pintype "output"))
    )
    (net (code "31") (name "CIN") (class "Default")
      (node (ref "R18") (pin "1") (pinfunction "1_1") (pintype "passive"))
      (node (ref "R19") (pin "1") (pinfunction "1_1") (pintype "passive"))
      (node (ref "U1") (pin "12") (pinfunction "P24_12") (pintype "bidirectional"))
      (node (ref "U15") (pin "13") (pinfunction "OUT_13") (pintype "open_collector"))
    )
    (net (code "32") (name "COLOR_REF") (class "Default")
      (node (ref "IC2") (pin "6") (pinfunction "COLOR_REF_IN_6") (pintype "input"))
      (node (ref "U11") (pin "9") (pinfunction "CHB_9") (pintype "output"))
    )
    (net (code "33") (name "CSS") (class "Default")
      (node (ref "U11") (pin "39") (pinfunction "CSS_39") (pintype "input"))
      (node (ref "U8") (pin "12") (pinfunction "Q5_12") (pintype "output"))
    )
    (net (code "34") (name "D0") (class "Default")
      (node (ref "E.") (pin "3") (pinfunction "P_3") (pintype "bidirectional"))
      (node (ref "U1") (pin "37") (pinfunction "D0/A0_37") (pintype "bidirectional"))
      (node (ref "U14") (pin "3") (pinfunction "OUT1_3") (pintype "tri_state"))
      (node (ref "U2") (pin "7") (pinfunction "3D_7") (pintype "input"))
      (node (ref "U3") (pin "11") (pinfunction "O0_11") (pintype "tri_state"))
      (node (ref "U7") (pin "9") (pinfunction "A8_9") (pintype "bidirectional"))
    )
    (net (code "35") (name "D1") (class "Default")
      (node (ref "E.") (pin "4") (pinfunction "P_4") (pintype "bidirectional"))
      (node (ref "U1") (pin "36") (pinfunction "D1/A1_36") (pintype "bidirectional"))
      (node (ref "U14") (pin "5") (pinfunction "OUT2_5") (pintype "tri_state"))
      (node (ref "U2") (pin "17") (pinfunction "7D_17") (pintype "input"))
      (node (ref "U3") (pin "12") (pinfunction "O1_12") (pintype "tri_state"))
      (node (ref "U7") (pin "8") (pinfunction "A7_8") (pintype "bidirectional"))
    )
    (net (code "36") (name "D2") (class "Default")
      (node (ref "E.") (pin "5") (pinfunction "P_5") (pintype "bidirectional"))
      (node (ref "U1") (pin "35") (pinfunction "D2/A2_35") (pintype "bidirectional"))
      (node (ref "U14") (pin "7") (pinfunction "OUT3_7") (pintype "tri_state"))
      (node (ref "U2") (pin "18") (pinfunction "8D_18") (pintype "input"))
      (node (ref "U3") (pin "13") (pinfunction "O2_13") (pintype "tri_state"))
      (node (ref "U7") (pin "7") (pinfunction "A6_7") (pintype "bidirectional"))
      (node (ref "U8") (pin "11") (pinfunction "D4_11") (pintype "input"))
    )
    (net (code "37") (name "D3") (class "Default")
      (node (ref "E.") (pin "6") (pinfunction "P_6") (pintype "bidirectional"))
      (node (ref "U1") (pin "34") (pinfunction "D3/A3_34") (pintype "bidirectional"))
      (node (ref "U14") (pin "9") (pinfunction "OUT4_9") (pintype "tri_state"))
      (node (ref "U2") (pin "3") (pinfunction "1D_3") (pintype "input"))
      (node (ref "U3") (pin "15") (pinfunction "O3_15") (pintype "tri_state"))
      (node (ref "U7") (pin "6") (pinfunction "A5_6") (pintype "bidirectional"))
      (node (ref "U8") (pin "3") (pinfunction "D1_3") (pintype "input"))
    )
    (net (code "38") (name "D4") (class "Default")
      (node (ref "E.") (pin "7") (pinfunction "P_7") (pintype "bidirectional"))
      (node (ref "U1") (pin "33") (pinfunction "D4/A4_33") (pintype "bidirectional"))
      (node (ref "U14") (pin "11") (pinfunction "OUT5_11") (pintype "tri_state"))
      (node (ref "U2") (pin "4") (pinfunction "2D_4") (pintype "input"))
      (node (ref "U3") (pin "16") (pinfunction "O4_16") (pintype "tri_state"))
      (node (ref "U7") (pin "5") (pinfunction "A4_5") (pintype "bidirectional"))
      (node (ref "U8") (pin "4") (pinfunction "D2_4") (pintype "input"))
    )
    (net (code "39") (name "D5") (class "Default")
      (node (ref "E.") (pin "8") (pinfunction "P_8") (pintype "bidirectional"))
      (node (ref "U1") (pin "32") (pinfunction "D5/A5_32") (pintype "bidirectional"))
      (node (ref "U14") (pin "13") (pinfunction "OUT6_13") (pintype "tri_state"))
      (node (ref "U2") (pin "8") (pinfunction "4D_8") (pintype "input"))
      (node (ref "U3") (pin "17") (pinfunction "O5_17") (pintype "tri_state"))
      (node (ref "U7") (pin "4") (pinfunction "A3_4") (pintype "bidirectional"))
      (node (ref "U8") (pin "6") (pinfunction "D3_6") (pintype "input"))
    )
    (net (code "40") (name "D6") (class "Default")
      (node (ref "E.") (pin "9") (pinfunction "P_9") (pintype "bidirectional"))
      (node (ref "U1") (pin "31") (pinfunction "D6/A6_31") (pintype "bidirectional"))
      (node (ref "U2") (pin "13") (pinfunction "5D_13") (pintype "input"))
      (node (ref "U3") (pin "18") (pinfunction "O6_18") (pintype "tri_state"))
      (node (ref "U7") (pin "3") (pinfunction "A2_3") (pintype "bidirectional"))
      (node (ref "U8") (pin "13") (pinfunction "D5_13") (pintype "input"))
    )
    (net (code "41") (name "D7") (class "Default")
      (node (ref "E.") (pin "10") (pinfunction "P_10") (pintype "bidirectional"))
      (node (ref "U1") (pin "30") (pinfunction "D7/A7_30") (pintype "bidirectional"))
      (node (ref "U2") (pin "14") (pinfunction "6D_14") (pintype "input"))
      (node (ref "U3") (pin "19") (pinfunction "O7_19") (pintype "tri_state"))
      (node (ref "U7") (pin "2") (pinfunction "A1_2") (pintype "bidirectional"))
      (node (ref "U8") (pin "14") (pinfunction "D6_14") (pintype "input"))
    )
    (net (code "42") (name "E") (class "Default")
      (node (ref "E.") (pin "28") (pinfunction "P_28") (pintype "bidirectional"))
      (node (ref "U1") (pin "40") (pinfunction "E_40") (pintype "output"))
      (node (ref "U18") (pin "1") (pinfunction "CLR_1") (pintype "input"))
      (node (ref "U4") (pin "1") (pinfunction "1C_1") (pintype "input"))
    )
    (net (code "43") (name "EAR") (class "Default")
      (node (ref "FB5") (pin "2") (pinfunction "2_2") (pintype "passive"))
      (node (ref "J1") (pin "4") (pinfunction "4_4") (pintype "passive"))
    )
    (net (code "44") (name "GM0") (class "Default")
      (node (ref "U11") (pin "30") (pinfunction "GM0_30") (pintype "input"))
      (node (ref "U8") (pin "5") (pinfunction "Q2_5") (pintype "output"))
    )
    (net (code "45") (name "GM1") (class "Default")
      (node (ref "U11") (pin "29") (pinfunction "GM1_29") (pintype "input"))
      (node (ref "U8") (pin "2") (pinfunction "Q1_2") (pintype "output"))
    )
    (net (code "46") (name "GM2") (class "Default")
      (node (ref "U11") (pin "27") (pinfunction "GM2_27") (pintype "input"))
      (node (ref "U11") (pin "31") (pinfunction "~{INT}/EXT_31") (pintype "input"))
      (node (ref "U8") (pin "10") (pinfunction "Q4_10") (pintype "output"))
    )
    (net (code "47") (name "GND") (class "Default")
      (node (ref "C1") (pin "-") (pinfunction "-_-") (pintype "passive"))
      (node (ref "C102") (pin "-") (pinfunction "A_-") (pintype "passive"))
      (node (ref "C103") (pin "2") (pinfunction "2_2") (pintype "passive"))
      (node (ref "C107") (pin "2") (pinfunction "2_2") (pintype "passive"))
      (node (ref "C108") (pin "2") (pinfunction "2_2") (pintype "passive"))
      (node (ref "C11") (pin "2") (pinfunction "2_2") (pintype "passive"))
      (node (ref "C111") (pin "2") (pinfunction "2_2") (pintype "passive"))
      (node (ref "C112") (pin "2") (pinfunction "2_2") (pintype "passive"))
      (node (ref "C114") (pin "2") (pinfunction "2_2") (pintype "passive"))
      (node (ref "C115") (pin "2") (pinfunction "2_2") (pintype "passive"))
      (node (ref "C116") (pin "2") (pinfunction "2_2") (pintype "passive"))
      (node (ref "C119") (pin "2") (pinfunction "2_2") (pintype "passive"))
      (node (ref "C12") (pin "1") (pinfunction "1_1") (pintype "passive"))
      (node (ref "C122") (pin "2") (pinfunction "2_2") (pintype "passive"))
      (node (ref "C13") (pin "2") (pinfunction "2_2") (pintype "passive"))
      (node (ref "C14") (pin "2") (pinfunction "2_2") (pintype "passive"))
      (node (ref "C15") (pin "2") (pinfunction "2_2") (pintype "passive"))
      (node (ref "C16") (pin "2") (pinfunction "2_2") (pintype "passive"))
      (node (ref "C17") (pin "2") (pinfunction "2_2") (pintype "passive"))
      (node (ref "C18") (pin "2") (pinfunction "2_2") (pintype "passive"))
      (node (ref "C19") (pin "2") (pinfunction "2_2") (pintype "passive"))
      (node (ref "C2") (pin "-") (pinfunction "-_-") (pintype "passive"))
      (node (ref "C20") (pin "2") (pinfunction "2_2") (pintype "passive"))
      (node (ref "C21") (pin "2") (pinfunction "2_2") (pintype "passive"))
      (node (ref "C22") (pin "2") (pinfunction "2_2") (pintype "passive"))
      (node (ref "C23") (pin "2") (pinfunction "2_2") (pintype "passive"))
      (node (ref "C24") (pin "2") (pinfunction "2_2") (pintype "passive"))
      (node (ref "C25") (pin "2") (pinfunction "2_2") (pintype "passive"))
      (node (ref "C26") (pin "2") (pinfunction "2_2") (pintype "passive"))
      (node (ref "C27") (pin "2") (pinfunction "2_2") (pintype "passive"))
      (node (ref "C28") (pin "2") (pinfunction "2_2") (pintype "passive"))
      (node (ref "C29") (pin "2") (pinfunction "2_2") (pintype "passive"))
      (node (ref "C30") (pin "2") (pinfunction "2_2") (pintype "passive"))
      (node (ref "C31") (pin "2") (pinfunction "2_2") (pintype "passive"))
      (node (ref "C32") (pin "2") (pinfunction "2_2") (pintype "passive"))
      (node (ref "C33") (pin "2") (pinfunction "2_2") (pintype "passive"))
      (node (ref "C4") (pin "+") (pinfunction "+_+") (pintype "passive"))
      (node (ref "C5") (pin "2") (pinfunction "2_2") (pintype "passive"))
      (node (ref "C6") (pin "2") (pinfunction "2_2") (pintype "passive"))
      (node (ref "C7") (pin "2") (pinfunction "2_2") (pintype "passive"))
      (node (ref "C8") (pin "-") (pinfunction "-_-") (pintype "passive"))
      (node (ref "D1") (pin "-") (pinfunction "-_-") (pintype "passive"))
      (node (ref "D102") (pin "A") (pinfunction "A_A") (pintype "passive"))
      (node (ref "D2") (pin "C") (pinfunction "C_C") (pintype "passive"))
      (node (ref "D6") (pin "A") (pinfunction "A_A") (pintype "passive"))
      (node (ref "E.") (pin "1") (pinfunction "P_1") (pintype "bidirectional"))
      (node (ref "E.") (pin "2") (pinfunction "P_2") (pintype "bidirectional"))
      (node (ref "E.") (pin "33") (pinfunction "P_33") (pintype "bidirectional"))
      (node (ref "E.") (pin "34") (pinfunction "P_34") (pintype "bidirectional"))
      (node (ref "GND") (pin "TP") (pinfunction "TP_TP") (pintype "input"))
      (node (ref "IC2") (pin "4") (pinfunction "GND_4") (pintype "power_in"))
      (node (ref "J1") (pin "2") (pinfunction "2_2") (pintype "passive"))
      (node (ref "J2") (pin "3") (pinfunction "3_3") (pintype "passive"))
      (node (ref "L101") (pin "1") (pinfunction "1_1") (pintype "passive"))
      (node (ref "L102") (pin "1") (pinfunction "1_1") (pintype "passive"))
      (node (ref "L103") (pin "1") (pinfunction "1_1") (pintype "passive"))
      (node (ref "R106") (pin "1") (pinfunction "1_1") (pintype "passive"))
      (node (ref "R11") (pin "1") (pinfunction "1_1") (pintype "passive"))
      (node (ref "R116") (pin "1") (pinfunction "1_1") (pintype "passive"))
      (node (ref "R117") (pin "1") (pinfunction "1_1") (pintype "passive"))
      (node (ref "R119") (pin "2") (pinfunction "2_2") (pintype "passive"))
      (node (ref "R12") (pin "1") (pinfunction "1_1") (pintype "passive"))
      (node (ref "R17") (pin "1") (pinfunction "1_1") (pintype "passive"))
      (node (ref "R3") (pin "1") (pinfunction "1_1") (pintype "passive"))
      (node (ref "R4") (pin "1") (pinfunction "1_1") (pintype "passive"))
      (node (ref "R6") (pin "1") (pinfunction "1_1") (pintype "passive"))
      (node (ref "R7") (pin "1") (pinfunction "1_1") (pintype "passive"))
      (node (ref "S1") (pin "1") (pinfunction "P_1") (pintype "passive"))
      (node (ref "S3") (pin "3") (pinfunction "S_3") (pintype "passive"))
      (node (ref "T101") (pin "3") (pinfunction "E2_3") (pintype "passive"))
      (node (ref "U1") (pin "1") (pinfunction "VSS_1") (pintype "power_in"))
      (node (ref "U1") (pin "2") (pinfunction "XTAL1_2") (pintype "bidirectional"))
      (node (ref "U10") (pin "12") (pinfunction "GND_12") (pintype "power_in"))
      (node (ref "U10") (pin "20") (pinfunction "~{OE}_20") (pintype "input"))
      (node (ref "U11") (pin "1") (pinfunction "GND_1") (pintype "power_in"))
      (node (ref "U12") (pin "7") (pinfunction "GND_7") (pintype "power_in"))
      (node (ref "U13") (pin "7") (pinfunction "GND_7") (pintype "power_in"))
      (node (ref "U14") (pin "8") (pinfunction "VSS_8") (pintype "power_in"))
      (node (ref "U17") (pin "GND") (pinfunction "GND_GND") (pintype "input"))
      (node (ref "U18") (pin "7") (pinfunction "GND_7") (pintype "power_in"))
      (node (ref "U19") (pin "12") (pinfunction "K_12") (pintype "input"))
      (node (ref "U19") (pin "13") (pinfunction "GND_13") (pintype "power_in"))
      (node (ref "U19") (pin "16") (pinfunction "K_16") (pintype "input"))
      (node (ref "U2") (pin "1") (pinfunction "OC_1") (pintype "input"))
      (node (ref "U2") (pin "10") (pinfunction "GND_10") (pintype "power_in"))
      (node (ref "U20") (pin "7") (pinfunction "GND_7") (pintype "power_in"))
      (node (ref "U3") (pin "14") (pinfunction "GND_14") (pintype "power_in"))
      (node (ref "U3") (pin "2") (pinfunction "~{CS1}_2") (pintype "input"))
      (node (ref "U3") (pin "27") (pinfunction "~{CS2}_27") (pintype "input"))
      (node (ref "U4") (pin "8") (pinfunction "GND_8") (pintype "power_in"))
      (node (ref "U5") (pin "8") (pinfunction "GND_8") (pintype "power_in"))
      (node (ref "U6") (pin "8") (pinfunction "GND_8") (pintype "power_in"))
      (node (ref "U7") (pin "10") (pinfunction "GND_10") (pintype "power_in"))
      (node (ref "U8") (pin "8") (pinfunction "GND_8") (pintype "power_in"))
      (node (ref "U9") (pin "12") (pinfunction "GND_12") (pintype "power_in"))
      (node (ref "U9") (pin "20") (pinfunction "~{OE}_20") (pintype "input"))
      (node (ref "X1") (pin "2") (pinfunction "2_2") (pintype "passive"))
      (node (ref "X1") (pin "2@1") (pinfunction "2_2@1") (pintype "passive"))
      (node (ref "X1") (pin "2@2") (pinfunction "2_2@2") (pintype "passive"))
    )
    (net (code "48") (name "KR0") (class "Default")
      (node (ref "J5") (pin "1") (pinfunction "S_1") (pintype "passive"))
      (node (ref "U1") (pin "13") (pinfunction "P10_13") (pintype "bidirectional"))
    )
    (net (code "49") (name "KR1") (class "Default")
      (node (ref "J5") (pin "2") (pinfunction "S_2") (pintype "passive"))
      (node (ref "U1") (pin "14") (pinfunction "P11_14") (pintype "bidirectional"))
    )
    (net (code "50") (name "KR2") (class "Default")
      (node (ref "J5") (pin "3") (pinfunction "S_3") (pintype "passive"))
      (node (ref "U1") (pin "15") (pinfunction "P12_15") (pintype "bidirectional"))
    )
    (net (code "51") (name "KR3") (class "Default")
      (node (ref "J5") (pin "4") (pinfunction "S_4") (pintype "passive"))
      (node (ref "U1") (pin "16") (pinfunction "P13_16") (pintype "bidirectional"))
    )
    (net (code "52") (name "KR4") (class "Default")
      (node (ref "J5") (pin "5") (pinfunction "S_5") (pintype "passive"))
      (node (ref "U1") (pin "17") (pinfunction "P14_17") (pintype "bidirectional"))
    )
    (net (code "53") (name "KR5") (class "Default")
      (node (ref "J5") (pin "6") (pinfunction "S_6") (pintype "passive"))
      (node (ref "U1") (pin "18") (pinfunction "P15_18") (pintype "bidirectional"))
    )
    (net (code "54") (name "KR6") (class "Default")
      (node (ref "J5") (pin "7") (pinfunction "S_7") (pintype "passive"))
      (node (ref "U1") (pin "19") (pinfunction "P16_19") (pintype "bidirectional"))
    )
    (net (code "55") (name "KR7") (class "Default")
      (node (ref "J5") (pin "8") (pinfunction "S_8") (pintype "passive"))
      (node (ref "U1") (pin "20") (pinfunction "P17_20") (pintype "bidirectional"))
    )
    (net (code "56") (name "LUMA") (class "Default")
      (node (ref "C33") (pin "1") (pinfunction "1_1") (pintype "passive"))
      (node (ref "IC2") (pin "9") (pinfunction "LUMA_INPUT_9") (pintype "input"))
      (node (ref "U11") (pin "28") (pinfunction "Y_28") (pintype "output"))
    )
    (net (code "57") (name "MIC") (class "Default")
      (node (ref "FB2") (pin "2") (pinfunction "2_2") (pintype "passive"))
      (node (ref "J1") (pin "5") (pinfunction "5_5") (pintype "passive"))
    )
    (net (code "58") (name "Net-(C3-Pad-)") (class "Default")
      (node (ref "C3") (pin "-") (pinfunction "-_-") (pintype "passive"))
      (node (ref "D2") (pin "A") (pinfunction "A_A") (pintype "passive"))
      (node (ref "D3") (pin "C") (pinfunction "C_C") (pintype "passive"))
    )
    (net (code "59") (name "Net-(C6-Pad1)") (class "Default")
      (node (ref "C6") (pin "1") (pinfunction "1_1") (pintype "passive"))
      (node (ref "FB2") (pin "1") (pinfunction "1_1") (pintype "passive"))
      (node (ref "R10") (pin "2") (pinfunction "2_2") (pintype "passive"))
      (node (ref "R11") (pin "2") (pinfunction "2_2") (pintype "passive"))
    )
    (net (code "60") (name "Net-(C7-Pad1)") (class "Default")
      (node (ref "C7") (pin "1") (pinfunction "1_1") (pintype "passive"))
      (node (ref "FB5") (pin "1") (pinfunction "1_1") (pintype "passive"))
      (node (ref "R12") (pin "2") (pinfunction "2_2") (pintype "passive"))
      (node (ref "R13") (pin "2") (pinfunction "2_2") (pintype "passive"))
    )
    (net (code "61") (name "Net-(C103-Pad1)") (class "Default")
      (node (ref "C103") (pin "1") (pinfunction "1_1") (pintype "passive"))
      (node (ref "R101") (pin "1") (pinfunction "1_1") (pintype "passive"))
      (node (ref "X101") (pin "2") (pinfunction "2_2") (pintype "passive"))
    )
    (net (code "62") (name "Net-(C105-Pad1)") (class "Default")
      (node (ref "C105") (pin "1") (pinfunction "1_1") (pintype "passive"))
      (node (ref "R102") (pin "1") (pinfunction "1_1") (pintype "passive"))
    )
    (net (code "63") (name "Net-(C106-Pad2)") (class "Default")
      (node (ref "C106") (pin "2") (pinfunction "2_2") (pintype "passive"))
      (node (ref "R103") (pin "1") (pinfunction "1_1") (pintype "passive"))
    )
    (net (code "64") (name "Net-(C107-Pad1)") (class "Default")
      (node (ref "C107") (pin "1") (pinfunction "1_1") (pintype "passive"))
      (node (ref "Q1") (pin "B") (pinfunction "B_B") (pintype "passive"))
      (node (ref "R105") (pin "2") (pinfunction "2_2") (pintype "passive"))
    )
    (net (code "65") (name "Net-(C108-Pad1)") (class "Default")
      (node (ref "C108") (pin "1") (pinfunction "1_1") (pintype "passive"))
      (node (ref "C109") (pin "2") (pinfunction "2_2") (pintype "passive"))
      (node (ref "Q1") (pin "E") (pinfunction "E_E") (pintype "passive"))
      (node (ref "R106") (pin "2") (pinfunction "2_2") (pintype "passive"))
    )
    (net (code "66") (name "Net-(C110-Pad2)") (class "Default")
      (node (ref "C110") (pin "2") (pinfunction "2_2") (pintype "passive"))
      (node (ref "D102") (pin "C") (pinfunction "C_C") (pintype "passive"))
      (node (ref "R107") (pin "2") (pinfunction "2_2") (pintype "passive"))
      (node (ref "R118") (pin "1") (pinfunction "1_1") (pintype "passive"))
      (node (ref "R119") (pin "1") (pinfunction "1_1") (pintype "passive"))
    )
    (net (code "67") (name "Net-(C112-Pad1)") (class "Default")
      (node (ref "C112") (pin "1") (pinfunction "1_1") (pintype "passive"))
      (node (ref "R109") (pin "2") (pinfunction "2_2") (pintype "passive"))
      (node (ref "R120") (pin "2") (pinfunction "2_2") (pintype "passive"))
    )
    (net (code "68") (name "Net-(C113-A)") (class "Default")
      (node (ref "C113") (pin "-") (pinfunction "A_-") (pintype "passive"))
      (node (ref "IC2") (pin "14") (pinfunction "RF_TANK2_14") (pintype "tri_state"))
      (node (ref "R111") (pin "1") (pinfunction "1_1") (pintype "passive"))
      (node (ref "T102") (pin "4") (pinfunction "E_4") (pintype "passive"))
    )
    (net (code "69") (name "Net-(C113-E)") (class "Default")
      (node (ref "C113") (pin "+") (pinfunction "E_+") (pintype "passive"))
      (node (ref "D101") (pin "C") (pinfunction "C_C") (pintype "passive"))
      (node (ref "R109") (pin "1") (pinfunction "1_1") (pintype "passive"))
    )
    (net (code "70") (name "Net-(C117-Pad2)") (class "Default")
      (node (ref "C117") (pin "2") (pinfunction "2_2") (pintype "passive"))
      (node (ref "C118") (pin "1") (pinfunction "1_1") (pintype "passive"))
      (node (ref "L101") (pin "2") (pinfunction "2_2") (pintype "passive"))
    )
    (net (code "71") (name "Net-(C118-Pad2)") (class "Default")
      (node (ref "C118") (pin "2") (pinfunction "2_2") (pintype "passive"))
      (node (ref "C119") (pin "1") (pinfunction "1_1") (pintype "passive"))
      (node (ref "C120") (pin "1") (pinfunction "1_1") (pintype "passive"))
      (node (ref "L102") (pin "2") (pinfunction "2_2") (pintype "passive"))
    )
    (net (code "72") (name "Net-(C120-Pad2)") (class "Default")
      (node (ref "C120") (pin "2") (pinfunction "2_2") (pintype "passive"))
      (node (ref "C121") (pin "1") (pinfunction "1_1") (pintype "passive"))
      (node (ref "L103") (pin "2") (pinfunction "2_2") (pintype "passive"))
    )
    (net (code "73") (name "Net-(C121-Pad2)") (class "Default")
      (node (ref "C121") (pin "2") (pinfunction "2_2") (pintype "passive"))
      (node (ref "C122") (pin "1") (pinfunction "1_1") (pintype "passive"))
      (node (ref "R115") (pin "1") (pinfunction "1_1") (pintype "passive"))
      (node (ref "R117") (pin "2") (pinfunction "2_2") (pintype "passive"))
    )
    (net (code "74") (name "Net-(C123-Pad1)") (class "Default")
      (node (ref "C123") (pin "1") (pinfunction "1_1") (pintype "passive"))
      (node (ref "R107") (pin "1") (pinfunction "1_1") (pintype "passive"))
    )
    (net (code "75") (name "Net-(D4-PadA)") (class "Default")
      (node (ref "D4") (pin "A") (pinfunction "A_A") (pintype "passive"))
      (node (ref "FB3") (pin "1") (pinfunction "1_1") (pintype "passive"))
    )
    (net (code "76") (name "Net-(D5-PadA)") (class "Default")
      (node (ref "D5") (pin "A") (pinfunction "A_A") (pintype "passive"))
      (node (ref "FB4") (pin "1") (pinfunction "1_1") (pintype "passive"))
    )
    (net (code "77") (name "Net-(D6-PadC)") (class "Default")
      (node (ref "D6") (pin "C") (pinfunction "C_C") (pintype "passive"))
      (node (ref "R13") (pin "1") (pinfunction "1_1") (pintype "passive"))
      (node (ref "R14") (pin "2") (pinfunction "2_2") (pintype "passive"))
    )
    (net (code "78") (name "Net-(FB1-Pad1)") (class "Default")
      (node (ref "FB1") (pin "1") (pinfunction "1_1") (pintype "passive"))
      (node (ref "R1") (pin "2") (pinfunction "2_2") (pintype "passive"))
    )
    (net (code "79") (name "Net-(IC2-CHROMA_INPUT)") (class "Default")
      (node (ref "C105") (pin "2") (pinfunction "2_2") (pintype "passive"))
      (node (ref "C106") (pin "1") (pinfunction "1_1") (pintype "passive"))
      (node (ref "IC2") (pin "10") (pinfunction "CHROMA_INPUT_10") (pintype "input"))
    )
    (net (code "80") (name "Net-(IC2-CHROMA_OUTPUT)") (class "Default")
      (node (ref "IC2") (pin "8") (pinfunction "CHROMA_OUTPUT_8") (pintype "output"))
      (node (ref "R102") (pin "2") (pinfunction "2_2") (pintype "passive"))
    )
    (net (code "81") (name "Net-(IC2-CLOCK_OUT)") (class "Default")
      (node (ref "IC2") (pin "1") (pinfunction "CLOCK_OUT_1") (pintype "output"))
      (node (ref "R101") (pin "2") (pinfunction "2_2") (pintype "passive"))
      (node (ref "U12") (pin "13") (pinfunction "I_13") (pintype "input"))
    )
    (net (code "82") (name "Net-(IC2-RF_OUT)") (class "Default")
      (node (ref "C116") (pin "1") (pinfunction "1_1") (pintype "passive"))
      (node (ref "C117") (pin "1") (pinfunction "1_1") (pintype "passive"))
      (node (ref "IC2") (pin "12") (pinfunction "RF_OUT_12") (pintype "output"))
      (node (ref "R113") (pin "1") (pinfunction "1_1") (pintype "passive"))
    )
    (net (code "83") (name "Net-(IC2-RF_TANK1)") (class "Default")
      (node (ref "D101") (pin "A") (pinfunction "A_A") (pintype "passive"))
      (node (ref "IC2") (pin "13") (pinfunction "RF_TANK1_13") (pintype "tri_state"))
      (node (ref "R110") (pin "1") (pinfunction "1_1") (pintype "passive"))
      (node (ref "T102") (pin "2") (pinfunction "A_2") (pintype "passive"))
    )
    (net (code "84") (name "Net-(IC2-VCC)") (class "Default")
      (node (ref "C115") (pin "1") (pinfunction "1_1") (pintype "passive"))
      (node (ref "IC2") (pin "11") (pinfunction "VCC_11") (pintype "power_in"))
      (node (ref "L104") (pin "2") (pinfunction "2_2") (pintype "passive"))
      (node (ref "R112") (pin "1") (pinfunction "1_1") (pintype "passive"))
      (node (ref "R113") (pin "2") (pinfunction "2_2") (pintype "passive"))
    )
    (net (code "85") (name "Net-(J1-Pad1)") (class "Default")
      (node (ref "J1") (pin "1") (pinfunction "1_1") (pintype "passive"))
      (node (ref "J1") (pin "3") (pinfunction "3_3") (pintype "passive"))
    )
    (net (code "86") (name "Net-(J4A-S)") (class "Default")
      (node (ref "J4") (pin "1") (pinfunction "S_1") (pintype "passive"))
      (node (ref "RN1") (pin "2") (pinfunction "2_2") (pintype "passive"))
      (node (ref "U14") (pin "2") (pinfunction "IN1_2") (pintype "input"))
    )
    (net (code "87") (name "Net-(J4B-S)") (class "Default")
      (node (ref "J4") (pin "2") (pinfunction "S_2") (pintype "passive"))
      (node (ref "RN1") (pin "3") (pinfunction "3_3") (pintype "passive"))
      (node (ref "U14") (pin "4") (pinfunction "IN2_4") (pintype "input"))
    )
    (net (code "88") (name "Net-(J4D-S)") (class "Default")
      (node (ref "J4") (pin "4") (pinfunction "S_4") (pintype "passive"))
      (node (ref "RN1") (pin "4") (pinfunction "4_4") (pintype "passive"))
      (node (ref "U14") (pin "6") (pinfunction "IN3_6") (pintype "input"))
    )
    (net (code "89") (name "Net-(J4E-S)") (class "Default")
      (node (ref "J4") (pin "5") (pinfunction "S_5") (pintype "passive"))
      (node (ref "RN1") (pin "5") (pinfunction "5_5") (pintype "passive"))
      (node (ref "U14") (pin "10") (pinfunction "IN4_10") (pintype "input"))
    )
    (net (code "90") (name "Net-(J4F-S)") (class "Default")
      (node (ref "J4") (pin "6") (pinfunction "S_6") (pintype "passive"))
      (node (ref "RN1") (pin "6") (pinfunction "6_6") (pintype "passive"))
      (node (ref "U14") (pin "12") (pinfunction "IN5_12") (pintype "input"))
    )
    (net (code "91") (name "Net-(J4G-S)") (class "Default")
      (node (ref "J4") (pin "7") (pinfunction "S_7") (pintype "passive"))
      (node (ref "RN1") (pin "7") (pinfunction "7_7") (pintype "passive"))
      (node (ref "U14") (pin "14") (pinfunction "IN6_14") (pintype "input"))
    )
    (net (code "92") (name "Net-(L104-Pad1)") (class "Default")
      (node (ref "L104") (pin "1") (pinfunction "1_1") (pintype "passive"))
      (node (ref "L105") (pin "2") (pinfunction "2_2") (pintype "passive"))
      (node (ref "R108") (pin "1") (pinfunction "1_1") (pintype "passive"))
      (node (ref "R118") (pin "2") (pinfunction "2_2") (pintype "passive"))
      (node (ref "R120") (pin "1") (pinfunction "1_1") (pintype "passive"))
    )
    (net (code "93") (name "Net-(R115-Pad2)") (class "Default")
      (node (ref "R115") (pin "2") (pinfunction "2_2") (pintype "passive"))
      (node (ref "R116") (pin "2") (pinfunction "2_2") (pintype "passive"))
      (node (ref "X1") (pin "1") (pinfunction "1_1") (pintype "passive"))
    )
    (net (code "94") (name "Net-(S1-S)") (class "Default")
      (node (ref "C8") (pin "+") (pinfunction "+_+") (pintype "passive"))
      (node (ref "D9") (pin "A") (pinfunction "A_A") (pintype "passive"))
      (node (ref "R24") (pin "2") (pinfunction "2_2") (pintype "passive"))
      (node (ref "S1") (pin "2") (pinfunction "S_2") (pintype "passive"))
      (node (ref "U12") (pin "1") (pinfunction "I_1") (pintype "input"))
    )
    (net (code "95") (name "Net-(S2A-P)") (class "Default")
      (node (ref "J3") (pin "2") (pinfunction "2_2") (pintype "passive"))
      (node (ref "S2") (pin "2") (pinfunction "P_2") (pintype "passive"))
    )
    (net (code "96") (name "Net-(S2A-S)") (class "Default")
      (node (ref "C11") (pin "1") (pinfunction "1_1") (pintype "passive"))
      (node (ref "C9") (pin "1") (pinfunction "1_1") (pintype "passive"))
      (node (ref "D1") (pin "AC1") (pinfunction "AC1_AC1") (pintype "passive"))
      (node (ref "S2") (pin "3") (pinfunction "S_3") (pintype "passive"))
    )
    (net (code "97") (name "Net-(S2B-P)") (class "Default")
      (node (ref "J3") (pin "1") (pinfunction "1_1") (pintype "passive"))
      (node (ref "S2") (pin "5") (pinfunction "P_5") (pintype "passive"))
    )
    (net (code "98") (name "Net-(S2B-S)") (class "Default")
      (node (ref "C10") (pin "2") (pinfunction "2_2") (pintype "passive"))
      (node (ref "C12") (pin "2") (pinfunction "2_2") (pintype "passive"))
      (node (ref "C3") (pin "+") (pinfunction "+_+") (pintype "passive"))
      (node (ref "D1") (pin "AC2") (pinfunction "AC2_AC2") (pintype "passive"))
      (node (ref "S2") (pin "6") (pinfunction "S_6") (pintype "passive"))
    )
    (net (code "99") (name "Net-(S3-P)") (class "Default")
      (node (ref "C114") (pin "1") (pinfunction "1_1") (pintype "passive"))
      (node (ref "R110") (pin "2") (pinfunction "2_2") (pintype "passive"))
      (node (ref "R111") (pin "2") (pinfunction "2_2") (pintype "passive"))
      (node (ref "R112") (pin "2") (pinfunction "2_2") (pintype "passive"))
      (node (ref "S3") (pin "2") (pinfunction "P_2") (pintype "passive"))
    )
    (net (code "100") (name "Net-(T101A-A1)") (class "Default")
      (node (ref "C109") (pin "1") (pinfunction "1_1") (pintype "passive"))
      (node (ref "C110") (pin "1") (pinfunction "1_1") (pintype "passive"))
      (node (ref "Q1") (pin "C") (pinfunction "C_C") (pintype "passive"))
      (node (ref "T101") (pin "2") (pinfunction "A1_2") (pintype "passive"))
    )
    (net (code "101") (name "Net-(T101A-A2)") (class "Default")
      (node (ref "R103") (pin "2") (pinfunction "2_2") (pintype "passive"))
      (node (ref "T101") (pin "4") (pinfunction "A2_4") (pintype "passive"))
    )
    (net (code "102") (name "Net-(T101A-E1)") (class "Default")
      (node (ref "C111") (pin "1") (pinfunction "1_1") (pintype "passive"))
      (node (ref "R105") (pin "1") (pinfunction "1_1") (pintype "passive"))
      (node (ref "R108") (pin "2") (pinfunction "2_2") (pintype "passive"))
      (node (ref "T101") (pin "1") (pinfunction "E1_1") (pintype "passive"))
    )
    (net (code "103") (name "Net-(U1-~{IRQ1})") (class "Default")
      (node (ref "R23") (pin "2") (pinfunction "2_2") (pintype "passive"))
      (node (ref "U1") (pin "5") (pinfunction "~{IRQ1}_5") (pintype "input"))
    )
    (net (code "104") (name "Net-(U11A-~{HS})") (class "Default")
      (node (ref "U11") (pin "38") (pinfunction "~{HS}_38") (pintype "output"))
      (node (ref "U19") (pin "6") (pinfunction "CLK_6") (pintype "input"))
    )
    (net (code "105") (name "Net-(U12D-O)") (class "Default")
      (node (ref "U12") (pin "2") (pinfunction "O_2") (pintype "output"))
      (node (ref "U12") (pin "3") (pinfunction "I_3") (pintype "input"))
    )
    (net (code "106") (name "Net-(U13A-I1)") (class "Default")
      (node (ref "U13") (pin "2") (pinfunction "I1_2") (pintype "input"))
      (node (ref "U4") (pin "10") (pinfunction "2Y1_10") (pintype "output"))
    )
    (net (code "107") (name "Net-(U13B-I1)") (class "Default")
      (node (ref "U13") (pin "5") (pinfunction "I1_5") (pintype "input"))
      (node (ref "U18") (pin "9") (pinfunction "Q_9") (pintype "output"))
    )
    (net (code "108") (name "Net-(U13C-I1)") (class "Default")
      (node (ref "U13") (pin "10") (pinfunction "I1_10") (pintype "input"))
      (node (ref "U13") (pin "13") (pinfunction "I1_13") (pintype "input"))
      (node (ref "U4") (pin "5") (pinfunction "1Y2_5") (pintype "output"))
    )
    (net (code "109") (name "Net-(U15A-+IN)") (class "Default")
      (node (ref "R5") (pin "1") (pinfunction "1_1") (pintype "passive"))
      (node (ref "R6") (pin "2") (pinfunction "2_2") (pintype "passive"))
      (node (ref "U15") (pin "5") (pinfunction "+IN_5") (pintype "input"))
      (node (ref "U15") (pin "7") (pinfunction "+IN_7") (pintype "input"))
    )
    (net (code "110") (name "Net-(U15A--IN)") (class "Default")
      (node (ref "D4") (pin "C") (pinfunction "C_C") (pintype "passive"))
      (node (ref "R4") (pin "2") (pinfunction "2_2") (pintype "passive"))
      (node (ref "U15") (pin "4") (pinfunction "-IN_4") (pintype "input"))
    )
    (net (code "111") (name "Net-(U15B--IN)") (class "Default")
      (node (ref "D5") (pin "C") (pinfunction "C_C") (pintype "passive"))
      (node (ref "R7") (pin "2") (pinfunction "2_2") (pintype "passive"))
      (node (ref "U15") (pin "6") (pinfunction "-IN_6") (pintype "input"))
    )
    (net (code "112") (name "Net-(U15D-+IN)") (class "Default")
      (node (ref "R16") (pin "1") (pinfunction "1_1") (pintype "passive"))
      (node (ref "R17") (pin "2") (pinfunction "2_2") (pintype "passive"))
      (node (ref "R18") (pin "2") (pinfunction "2_2") (pintype "passive"))
      (node (ref "U15") (pin "11") (pinfunction "+IN_11") (pintype "input"))
    )
    (net (code "113") (name "Net-(U15D--IN)") (class "Default")
      (node (ref "R14") (pin "1") (pinfunction "1_1") (pintype "passive"))
      (node (ref "R15") (pin "1") (pinfunction "1_1") (pintype "passive"))
      (node (ref "U15") (pin "10") (pinfunction "-IN_10") (pintype "input"))
    )
    (net (code "114") (name "Net-(U16-+IN)") (class "Default")
      (node (ref "R2") (pin "1") (pinfunction "1_1") (pintype "passive"))
      (node (ref "R3") (pin "2") (pinfunction "2_2") (pintype "passive"))
      (node (ref "U16") (pin "3") (pinfunction "+IN_3") (pintype "input"))
    )
    (net (code "115") (name "Net-(U16-OUT)") (class "Default")
      (node (ref "R1") (pin "1") (pinfunction "1_1") (pintype "passive"))
      (node (ref "U16") (pin "6") (pinfunction "OUT_6") (pintype "output"))
    )
    (net (code "116") (name "Net-(U18A-PRE)") (class "Default")
      (node (ref "R25") (pin "2") (pinfunction "2_2") (pintype "passive"))
      (node (ref "U18") (pin "10") (pinfunction "PRE_10") (pintype "input"))
      (node (ref "U18") (pin "13") (pinfunction "CLR_13") (pintype "input"))
      (node (ref "U18") (pin "4") (pinfunction "PRE_4") (pintype "input"))
      (node (ref "U19") (pin "2") (pinfunction "PRE_2") (pintype "input"))
      (node (ref "U19") (pin "4") (pinfunction "J_4") (pintype "input"))
      (node (ref "U19") (pin "7") (pinfunction "PRE_7") (pintype "input"))
      (node (ref "U19") (pin "9") (pinfunction "J_9") (pintype "input"))
    )
    (net (code "117") (name "Net-(U18B-D)") (class "Default")
      (node (ref "U18") (pin "12") (pinfunction "D_12") (pintype "input"))
      (node (ref "U19") (pin "15") (pinfunction "Q_15") (pintype "output"))
    )
    (net (code "118") (name "Net-(U18B-~{Q})") (class "Default")
      (node (ref "U18") (pin "8") (pinfunction "~{Q}_8") (pintype "output"))
      (node (ref "U19") (pin "3") (pinfunction "CLR_3") (pintype "input"))
    )
    (net (code "119") (name "Net-(U19A-CLK)") (class "Default")
      (node (ref "U19") (pin "1") (pinfunction "CLK_1") (pintype "input"))
      (node (ref "U19") (pin "10") (pinfunction "~{Q}_10") (pintype "output"))
    )
    (net (code "120") (name "Net-(U20A-O)") (class "Default")
      (node (ref "U20") (pin "3") (pinfunction "O_3") (pintype "output"))
      (node (ref "U4") (pin "14") (pinfunction "2G_14") (pintype "input"))
    )
    (net (code "121") (name "OSC-IN") (class "Default")
      (node (ref "C102") (pin "+") (pinfunction "E_+") (pintype "passive"))
      (node (ref "IC2") (pin "2") (pinfunction "OSC_IN_2") (pintype "tri_state"))
      (node (ref "R26") (pin "1") (pinfunction "1_1") (pintype "passive"))
      (node (ref "X101") (pin "1") (pinfunction "1_1") (pintype "passive"))
    )
    (net (code "122") (name "R2323-IN") (class "Default")
      (node (ref "D7") (pin "A") (pinfunction "A_A") (pintype "passive"))
      (node (ref "R8") (pin "1") (pinfunction "1_1") (pintype "passive"))
      (node (ref "U1") (pin "10") (pinfunction "P22_10") (pintype "bidirectional"))
      (node (ref "U15") (pin "2") (pinfunction "OUT_2") (pintype "open_collector"))
    )
    (net (code "123") (name "RS232{slash}CAS-OUT") (class "Default")
      (node (ref "D8") (pin "A") (pinfunction "A_A") (pintype "passive"))
      (node (ref "R10") (pin "1") (pinfunction "1_1") (pintype "passive"))
      (node (ref "U1") (pin "8") (pinfunction "P20_8") (pintype "bidirectional"))
      (node (ref "U16") (pin "2") (pinfunction "-IN_2") (pintype "input"))
    )
    (net (code "124") (name "RXD") (class "Default")
      (node (ref "FB3") (pin "2") (pinfunction "2_2") (pintype "passive"))
      (node (ref "J2") (pin "2") (pinfunction "2_2") (pintype "passive"))
    )
    (net (code "125") (name "R{slash}~{W}") (class "Default")
      (node (ref "E.") (pin "11") (pinfunction "P_11") (pintype "bidirectional"))
      (node (ref "U1") (pin "38") (pinfunction "R/~{W}_38") (pintype "output"))
      (node (ref "U12") (pin "5") (pinfunction "I_5") (pintype "input"))
      (node (ref "U13") (pin "1") (pinfunction "I0_1") (pintype "input"))
      (node (ref "U13") (pin "9") (pinfunction "I0_9") (pintype "input"))
    )
    (net (code "126") (name "SEL") (class "Default")
      (node (ref "E.") (pin "29") (pinfunction "P_29") (pintype "bidirectional"))
      (node (ref "R21") (pin "2") (pinfunction "2_2") (pintype "passive"))
      (node (ref "U12") (pin "9") (pinfunction "I_9") (pintype "input"))
    )
    (net (code "127") (name "SHIFT") (class "Default")
      (node (ref "J4") (pin "8") (pinfunction "S_8") (pintype "passive"))
      (node (ref "RN1") (pin "8") (pinfunction "8_8") (pintype "passive"))
      (node (ref "U1") (pin "9") (pinfunction "P21_9") (pintype "bidirectional"))
    )
    (net (code "128") (name "SOUND") (class "Default")
      (node (ref "C123") (pin "2") (pinfunction "2_2") (pintype "passive"))
      (node (ref "U8") (pin "15") (pinfunction "Q6_15") (pintype "output"))
    )
    (net (code "129") (name "TXD") (class "Default")
      (node (ref "FB1") (pin "2") (pinfunction "2_2") (pintype "passive"))
      (node (ref "J2") (pin "4") (pinfunction "4_4") (pintype "passive"))
    )
    (net (code "130") (name "VA0") (class "Default")
      (node (ref "U10") (pin "8") (pinfunction "A0_8") (pintype "input"))
      (node (ref "U11") (pin "22") (pinfunction "DA0_22") (pintype "output"))
      (node (ref "U6") (pin "7") (pinfunction "1Y3_7") (pintype "tri_state"))
      (node (ref "U9") (pin "8") (pinfunction "A0_8") (pintype "input"))
    )
    (net (code "131") (name "VA1") (class "Default")
      (node (ref "U10") (pin "7") (pinfunction "A1_7") (pintype "input"))
      (node (ref "U11") (pin "23") (pinfunction "DA1_23") (pintype "output"))
      (node (ref "U6") (pin "5") (pinfunction "1Y2_5") (pintype "tri_state"))
      (node (ref "U9") (pin "7") (pinfunction "A1_7") (pintype "input"))
    )
    (net (code "132") (name "VA2") (class "Default")
      (node (ref "U10") (pin "6") (pinfunction "A2_6") (pintype "input"))
      (node (ref "U11") (pin "24") (pinfunction "DA2_24") (pintype "output"))
      (node (ref "U6") (pin "3") (pinfunction "1Y1_3") (pintype "tri_state"))
      (node (ref "U9") (pin "6") (pinfunction "A2_6") (pintype "input"))
    )
    (net (code "133") (name "VA3") (class "Default")
      (node (ref "U10") (pin "5") (pinfunction "A3_5") (pintype "input"))
      (node (ref "U11") (pin "25") (pinfunction "DA3_25") (pintype "output"))
      (node (ref "U6") (pin "13") (pinfunction "2Y2_13") (pintype "tri_state"))
      (node (ref "U9") (pin "5") (pinfunction "A3_5") (pintype "input"))
    )
    (net (code "134") (name "VA4") (class "Default")
      (node (ref "U10") (pin "4") (pinfunction "A4_4") (pintype "input"))
      (node (ref "U11") (pin "26") (pinfunction "DA4_26") (pintype "output"))
      (node (ref "U6") (pin "11") (pinfunction "2Y1_11") (pintype "tri_state"))
      (node (ref "U9") (pin "4") (pinfunction "A4_4") (pintype "input"))
    )
    (net (code "135") (name "VA5") (class "Default")
      (node (ref "U10") (pin "3") (pinfunction "A5_3") (pintype "input"))
      (node (ref "U11") (pin "13") (pinfunction "DA5_13") (pintype "output"))
      (node (ref "U6") (pin "9") (pinfunction "1Y4_9") (pintype "tri_state"))
      (node (ref "U9") (pin "3") (pinfunction "A5_3") (pintype "input"))
    )
    (net (code "136") (name "VA6") (class "Default")
      (node (ref "U10") (pin "2") (pinfunction "A6_2") (pintype "input"))
      (node (ref "U11") (pin "14") (pinfunction "DA6_14") (pintype "output"))
      (node (ref "U5") (pin "7") (pinfunction "1Y3_7") (pintype "tri_state"))
      (node (ref "U9") (pin "2") (pinfunction "A6_2") (pintype "input"))
    )
    (net (code "137") (name "VA7") (class "Default")
      (node (ref "U10") (pin "1") (pinfunction "A7_1") (pintype "input"))
      (node (ref "U11") (pin "15") (pinfunction "DA7_15") (pintype "output"))
      (node (ref "U5") (pin "5") (pinfunction "1Y2_5") (pintype "tri_state"))
      (node (ref "U9") (pin "1") (pinfunction "A7_1") (pintype "input"))
    )
    (net (code "138") (name "VA8") (class "Default")
      (node (ref "U10") (pin "23") (pinfunction "A8_23") (pintype "input"))
      (node (ref "U11") (pin "16") (pinfunction "DA8_16") (pintype "output"))
      (node (ref "U5") (pin "3") (pinfunction "1Y1_3") (pintype "tri_state"))
      (node (ref "U9") (pin "23") (pinfunction "A8_23") (pintype "input"))
    )
    (net (code "139") (name "VA9") (class "Default")
      (node (ref "U10") (pin "22") (pinfunction "A9_22") (pintype "input"))
      (node (ref "U11") (pin "18") (pinfunction "DA9_18") (pintype "output"))
      (node (ref "U5") (pin "13") (pinfunction "2Y2_13") (pintype "tri_state"))
      (node (ref "U9") (pin "22") (pinfunction "A9_22") (pintype "input"))
    )
    (net (code "140") (name "VA10") (class "Default")
      (node (ref "U10") (pin "19") (pinfunction "A10_19") (pintype "input"))
      (node (ref "U11") (pin "19") (pinfunction "DA10_19") (pintype "output"))
      (node (ref "U5") (pin "11") (pinfunction "2Y1_11") (pintype "tri_state"))
      (node (ref "U9") (pin "19") (pinfunction "A10_19") (pintype "input"))
    )
    (net (code "141") (name "VA11") (class "Default")
      (node (ref "U11") (pin "20") (pinfunction "DA11_20") (pintype "output"))
      (node (ref "U12") (pin "11") (pinfunction "I_11") (pintype "input"))
      (node (ref "U5") (pin "9") (pinfunction "1Y4_9") (pintype "tri_state"))
      (node (ref "U9") (pin "18") (pinfunction "~{CS}_18") (pintype "input"))
    )
    (net (code "142") (name "VD0") (class "Default")
      (node (ref "U10") (pin "9") (pinfunction "I/O1_9") (pintype "bidirectional"))
      (node (ref "U11") (pin "3") (pinfunction "DD0_3") (pintype "bidirectional"))
      (node (ref "U7") (pin "11") (pinfunction "B8_11") (pintype "bidirectional"))
      (node (ref "U9") (pin "9") (pinfunction "I/O1_9") (pintype "bidirectional"))
    )
    (net (code "143") (name "VD1") (class "Default")
      (node (ref "U10") (pin "10") (pinfunction "I/O2_10") (pintype "bidirectional"))
      (node (ref "U11") (pin "4") (pinfunction "DD1_4") (pintype "bidirectional"))
      (node (ref "U7") (pin "12") (pinfunction "B7_12") (pintype "bidirectional"))
      (node (ref "U9") (pin "10") (pinfunction "I/O2_10") (pintype "bidirectional"))
    )
    (net (code "144") (name "VD2") (class "Default")
      (node (ref "U10") (pin "11") (pinfunction "I/O3_11") (pintype "bidirectional"))
      (node (ref "U11") (pin "5") (pinfunction "DD2_5") (pintype "bidirectional"))
      (node (ref "U7") (pin "13") (pinfunction "B6_13") (pintype "bidirectional"))
      (node (ref "U9") (pin "11") (pinfunction "I/O3_11") (pintype "bidirectional"))
    )
    (net (code "145") (name "VD3") (class "Default")
      (node (ref "U10") (pin "13") (pinfunction "I/O4_13") (pintype "bidirectional"))
      (node (ref "U11") (pin "6") (pinfunction "DD3_6") (pintype "bidirectional"))
      (node (ref "U7") (pin "14") (pinfunction "B5_14") (pintype "bidirectional"))
      (node (ref "U9") (pin "13") (pinfunction "I/O4_13") (pintype "bidirectional"))
    )
    (net (code "146") (name "VD4") (class "Default")
      (node (ref "U10") (pin "14") (pinfunction "I/O5_14") (pintype "bidirectional"))
      (node (ref "U11") (pin "7") (pinfunction "DD4_7") (pintype "bidirectional"))
      (node (ref "U7") (pin "15") (pinfunction "B4_15") (pintype "bidirectional"))
      (node (ref "U9") (pin "14") (pinfunction "I/O5_14") (pintype "bidirectional"))
    )
    (net (code "147") (name "VD5") (class "Default")
      (node (ref "U10") (pin "15") (pinfunction "I/O6_15") (pintype "bidirectional"))
      (node (ref "U11") (pin "8") (pinfunction "DD5_8") (pintype "bidirectional"))
      (node (ref "U7") (pin "16") (pinfunction "B3_16") (pintype "bidirectional"))
      (node (ref "U9") (pin "15") (pinfunction "I/O6_15") (pintype "bidirectional"))
    )
    (net (code "148") (name "VD6") (class "Default")
      (node (ref "U10") (pin "16") (pinfunction "I/O7_16") (pintype "bidirectional"))
      (node (ref "U11") (pin "2") (pinfunction "DD6_2") (pintype "bidirectional"))
      (node (ref "U11") (pin "32") (pinfunction "INV_32") (pintype "input"))
      (node (ref "U7") (pin "17") (pinfunction "B2_17") (pintype "bidirectional"))
      (node (ref "U9") (pin "16") (pinfunction "I/O7_16") (pintype "bidirectional"))
    )
    (net (code "149") (name "VD7") (class "Default")
      (node (ref "U10") (pin "17") (pinfunction "I/O8_17") (pintype "bidirectional"))
      (node (ref "U11") (pin "34") (pinfunction "~{A}/S_34") (pintype "input"))
      (node (ref "U11") (pin "40") (pinfunction "DD7_40") (pintype "bidirectional"))
      (node (ref "U7") (pin "18") (pinfunction "B1_18") (pintype "bidirectional"))
      (node (ref "U9") (pin "17") (pinfunction "I/O8_17") (pintype "bidirectional"))
    )
    (net (code "150") (name "VDG_CLOCK") (class "Default")
      (node (ref "TP2") (pin "TP") (pinfunction "TP_TP") (pintype "input"))
      (node (ref "U11") (pin "33") (pinfunction "CLK_33") (pintype "input"))
      (node (ref "U13") (pin "6") (pinfunction "O_6") (pintype "output"))
    )
    (net (code "151") (name "unconnected-(IC2-DUTY_CYCL_ADJ-Pad3)") (class "Default")
      (node (ref "IC2") (pin "3") (pinfunction "DUTY_CYCL_ADJ_3") (pintype "passive"))
    )
    (net (code "152") (name "unconnected-(J3-Pad3)") (class "Default")
      (node (ref "J3") (pin "3") (pinfunction "3_3") (pintype "passive"))
    )
    (net (code "153") (name "unconnected-(J4C-S-Pad3)") (class "Default")
      (node (ref "J4") (pin "3") (pinfunction "S_3") (pintype "passive"))
    )
    (net (code "154") (name "unconnected-(S2A-O-Pad1)") (class "Default")
      (node (ref "S2") (pin "1") (pinfunction "O_1") (pintype "passive"))
    )
    (net (code "155") (name "unconnected-(S2B-O-Pad4)") (class "Default")
      (node (ref "S2") (pin "4") (pinfunction "O_4") (pintype "passive"))
    )
    (net (code "156") (name "unconnected-(S3-O-Pad1)") (class "Default")
      (node (ref "S3") (pin "1") (pinfunction "O_1") (pintype "passive"))
    )
    (net (code "157") (name "unconnected-(U4A-1Y0-Pad7)") (class "Default")
      (node (ref "U4") (pin "7") (pinfunction "1Y0_7") (pintype "output"))
    )
    (net (code "158") (name "unconnected-(U4A-2Y0-Pad9)") (class "Default")
      (node (ref "U4") (pin "9") (pinfunction "2Y0_9") (pintype "output"))
    )
    (net (code "159") (name "unconnected-(U4A-2Y2-Pad11)") (class "Default")
      (node (ref "U4") (pin "11") (pinfunction "2Y2_11") (pintype "output"))
    )
    (net (code "160") (name "unconnected-(U4A-2Y3-Pad12)") (class "Default")
      (node (ref "U4") (pin "12") (pinfunction "2Y3_12") (pintype "output"))
    )
    (net (code "161") (name "unconnected-(U11A-DA12-Pad21)") (class "Default")
      (node (ref "U11") (pin "21") (pinfunction "DA12_21") (pintype "output"))
    )
    (net (code "162") (name "unconnected-(U11A-~{FS}-Pad37)") (class "Default")
      (node (ref "U11") (pin "37") (pinfunction "~{FS}_37") (pintype "output"))
    )
    (net (code "163") (name "unconnected-(U11A-~{RP}-Pad36)") (class "Default")
      (node (ref "U11") (pin "36") (pinfunction "~{RP}_36") (pintype "output"))
    )
    (net (code "164") (name "unconnected-(U16-ON1-Pad1)") (class "Default")
      (node (ref "U16") (pin "1") (pinfunction "ON1_1") (pintype "passive"))
    )
    (net (code "165") (name "unconnected-(U16-ON2-Pad5)") (class "Default")
      (node (ref "U16") (pin "5") (pinfunction "ON2_5") (pintype "passive"))
    )
    (net (code "166") (name "unconnected-(U16-OPT-Pad8)") (class "Default")
      (node (ref "U16") (pin "8") (pinfunction "OPT_8") (pintype "passive"))
    )
    (net (code "167") (name "unconnected-(U18A-Q-Pad5)") (class "Default")
      (node (ref "U18") (pin "5") (pinfunction "Q_5") (pintype "output"))
    )
    (net (code "168") (name "unconnected-(U19A-~{Q}-Pad14)") (class "Default")
      (node (ref "U19") (pin "14") (pinfunction "~{Q}_14") (pintype "output"))
    )
    (net (code "169") (name "unconnected-(U19B-Q-Pad11)") (class "Default")
      (node (ref "U19") (pin "11") (pinfunction "Q_11") (pintype "output"))
    )
    (net (code "170") (name "~{A}{slash}G") (class "Default")
      (node (ref "U11") (pin "35") (pinfunction "~{A}/G_35") (pintype "input"))
      (node (ref "U8") (pin "7") (pinfunction "Q3_7") (pintype "output"))
    )
    (net (code "171") (name "~{KEYRD}") (class "Default")
      (node (ref "U13") (pin "11") (pinfunction "O_11") (pintype "output"))
      (node (ref "U14") (pin "1") (pinfunction "~{DIS_A}_1") (pintype "input"))
      (node (ref "U14") (pin "15") (pinfunction "~{DIS_B}_15") (pintype "input"))
    )
    (net (code "172") (name "~{MS}") (class "Default")
      (node (ref "U11") (pin "12") (pinfunction "~{MS}_12") (pintype "input"))
      (node (ref "U4") (pin "6") (pinfunction "1Y1_6") (pintype "output"))
      (node (ref "U5") (pin "1") (pinfunction "1G_1") (pintype "input"))
      (node (ref "U5") (pin "15") (pinfunction "2G_15") (pintype "input"))
      (node (ref "U6") (pin "1") (pinfunction "1G_1") (pintype "input"))
      (node (ref "U6") (pin "15") (pinfunction "2G_15") (pintype "input"))
      (node (ref "U7") (pin "19") (pinfunction "G_19") (pintype "input"))
    )
    (net (code "173") (name "~{MW}") (class "Default")
      (node (ref "U10") (pin "21") (pinfunction "~{WE}_21") (pintype "input"))
      (node (ref "U13") (pin "3") (pinfunction "O_3") (pintype "output"))
      (node (ref "U9") (pin "21") (pinfunction "~{WE}_21") (pintype "input"))
    )
    (net (code "174") (name "~{NMI}") (class "Default")
      (node (ref "E.") (pin "31") (pinfunction "P_31") (pintype "bidirectional"))
      (node (ref "R22") (pin "2") (pinfunction "2_2") (pintype "passive"))
      (node (ref "U1") (pin "4") (pinfunction "~{NMI}_4") (pintype "input"))
    )
    (net (code "175") (name "~{RESET}") (class "Default")
      (node (ref "D7") (pin "C") (pinfunction "C_C") (pintype "passive"))
      (node (ref "D8") (pin "C") (pinfunction "C_C") (pintype "passive"))
      (node (ref "E.") (pin "30") (pinfunction "P_30") (pintype "bidirectional"))
      (node (ref "U1") (pin "6") (pinfunction "~{RESET}_6") (pintype "input"))
      (node (ref "U12") (pin "4") (pinfunction "O_4") (pintype "output"))
      (node (ref "U8") (pin "1") (pinfunction "CLR_1") (pintype "input"))
    )
    (net (code "176") (name "~{ROM_CS}") (class "Default")
      (node (ref "U3") (pin "22") (pinfunction "E/~{PGM}_22") (pintype "input"))
      (node (ref "U4") (pin "4") (pinfunction "1Y3_4") (pintype "output"))
    )
    (net (code "177") (name "~{R}{slash}W") (class "Default")
      (node (ref "U12") (pin "6") (pinfunction "O_6") (pintype "output"))
      (node (ref "U13") (pin "12") (pinfunction "I0_12") (pintype "input"))
      (node (ref "U7") (pin "1") (pinfunction "DIR_1") (pintype "input"))
    )
    (net (code "178") (name "~{SEL}") (class "Default")
      (node (ref "U12") (pin "8") (pinfunction "O_8") (pintype "output"))
      (node (ref "U20") (pin "1") (pinfunction "I0_1") (pintype "input"))
      (node (ref "U4") (pin "2") (pinfunction "1G_2") (pintype "input"))
    )
    (net (code "179") (name "~{VA11}") (class "Default")
      (node (ref "U10") (pin "18") (pinfunction "~{CS}_18") (pintype "input"))
      (node (ref "U12") (pin "10") (pinfunction "O_10") (pintype "output"))
    )
    (net (code "180") (name "~{VDG_CTL}") (class "Default")
      (node (ref "U13") (pin "8") (pinfunction "O_8") (pintype "output"))
      (node (ref "U8") (pin "9") (pinfunction "CLK_9") (pintype "input"))
    )
    (net (code "181") (name "~{WIN}") (class "Default")
      (node (ref "U18") (pin "2") (pinfunction "D_2") (pintype "input"))
      (node (ref "U18") (pin "6") (pinfunction "~{Q}_6") (pintype "output"))
      (node (ref "U19") (pin "8") (pinfunction "CLR_8") (pintype "input"))
      (node (ref "U4") (pin "15") (pinfunction "2C_15") (pintype "input"))
    )
  )
)
